# cfc-sensor-card.net
KiCad netlist of a schematic drawn in EAGLE
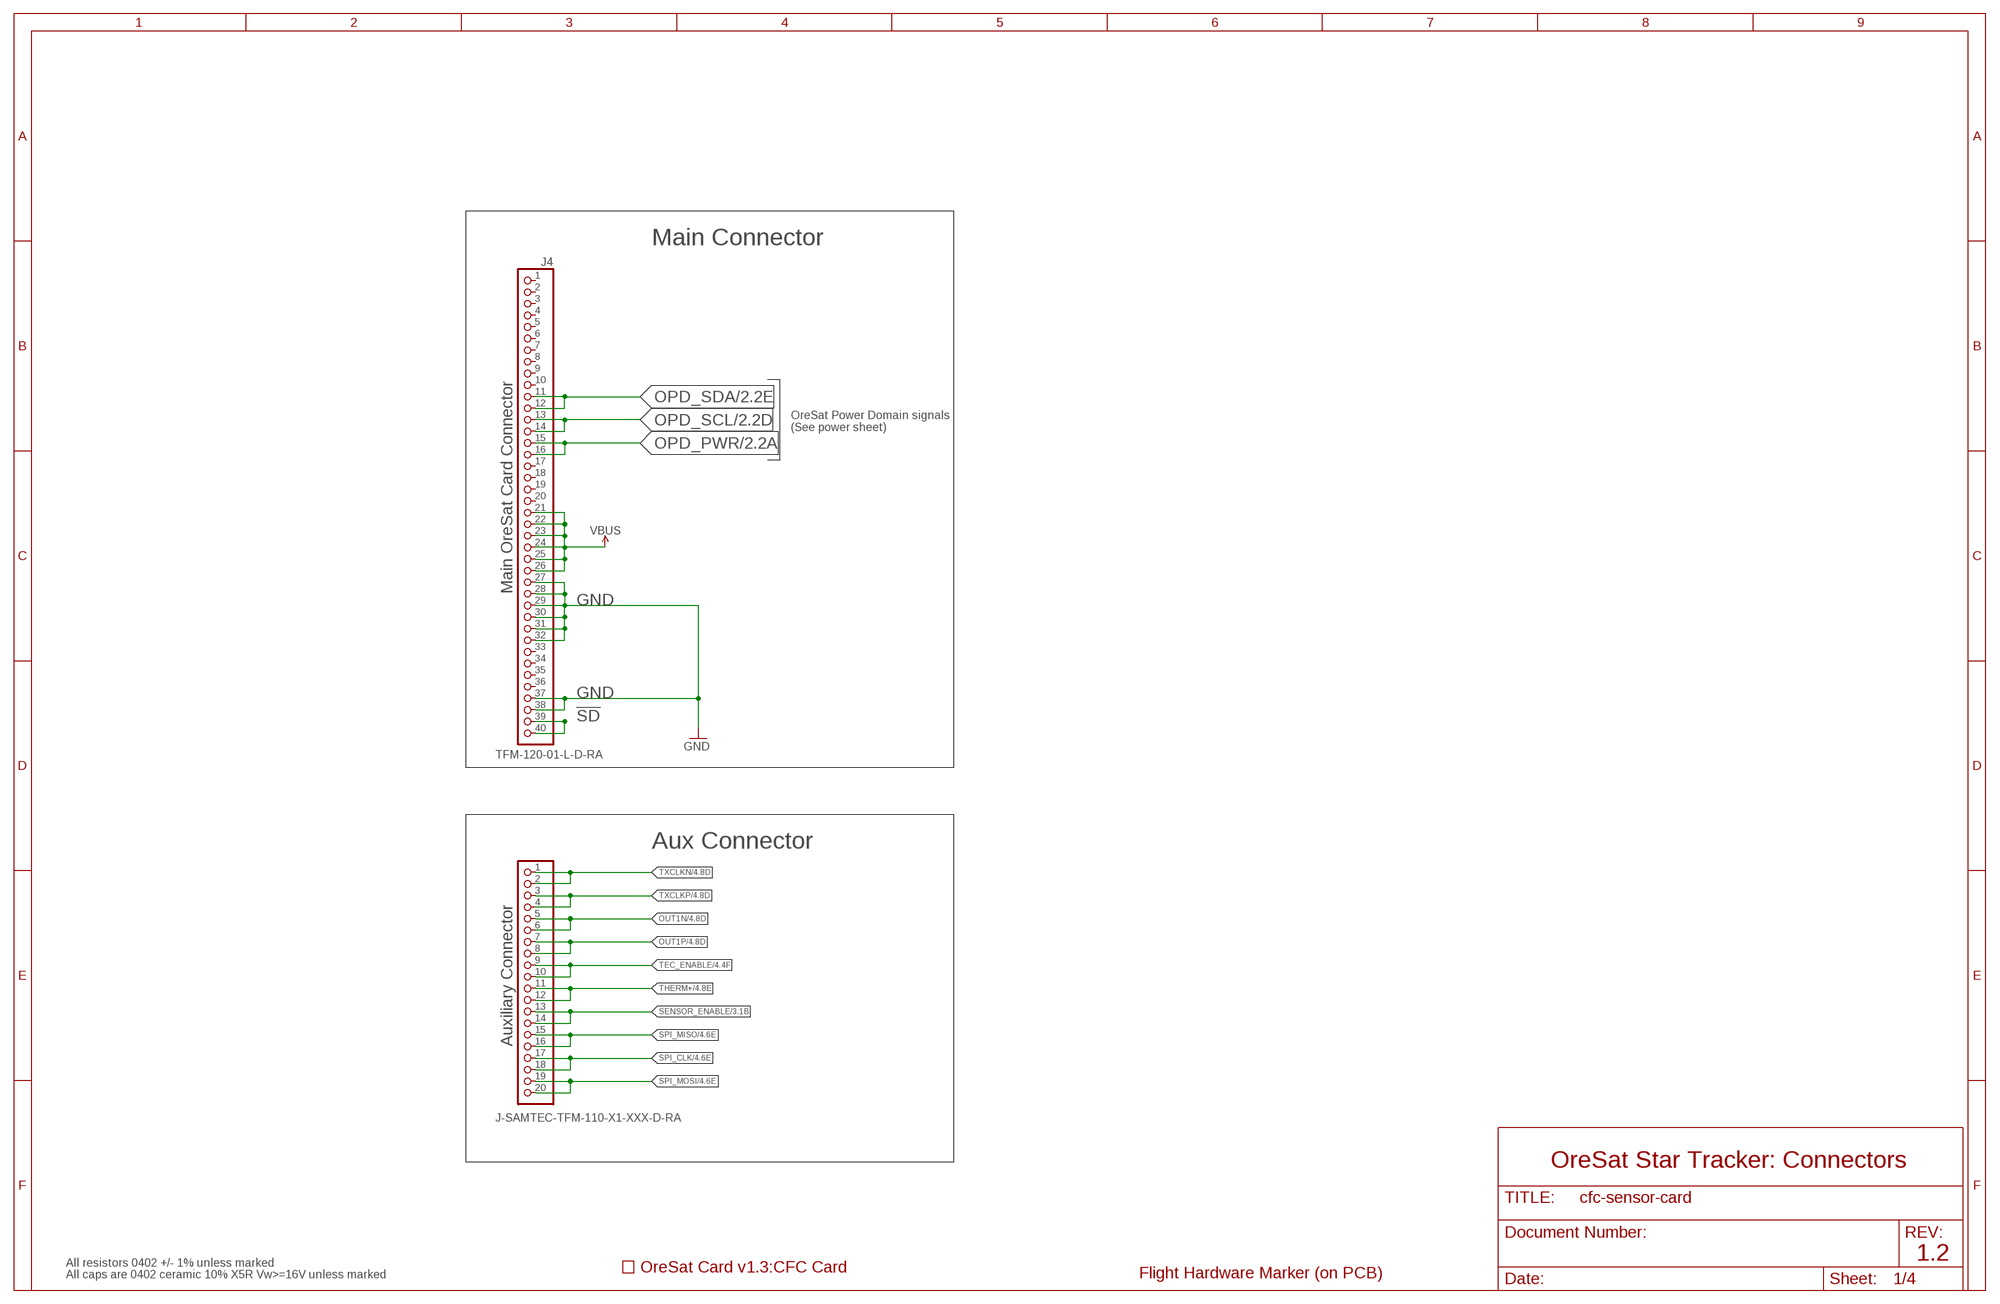
[diagram p0: schematic, sheet 1]
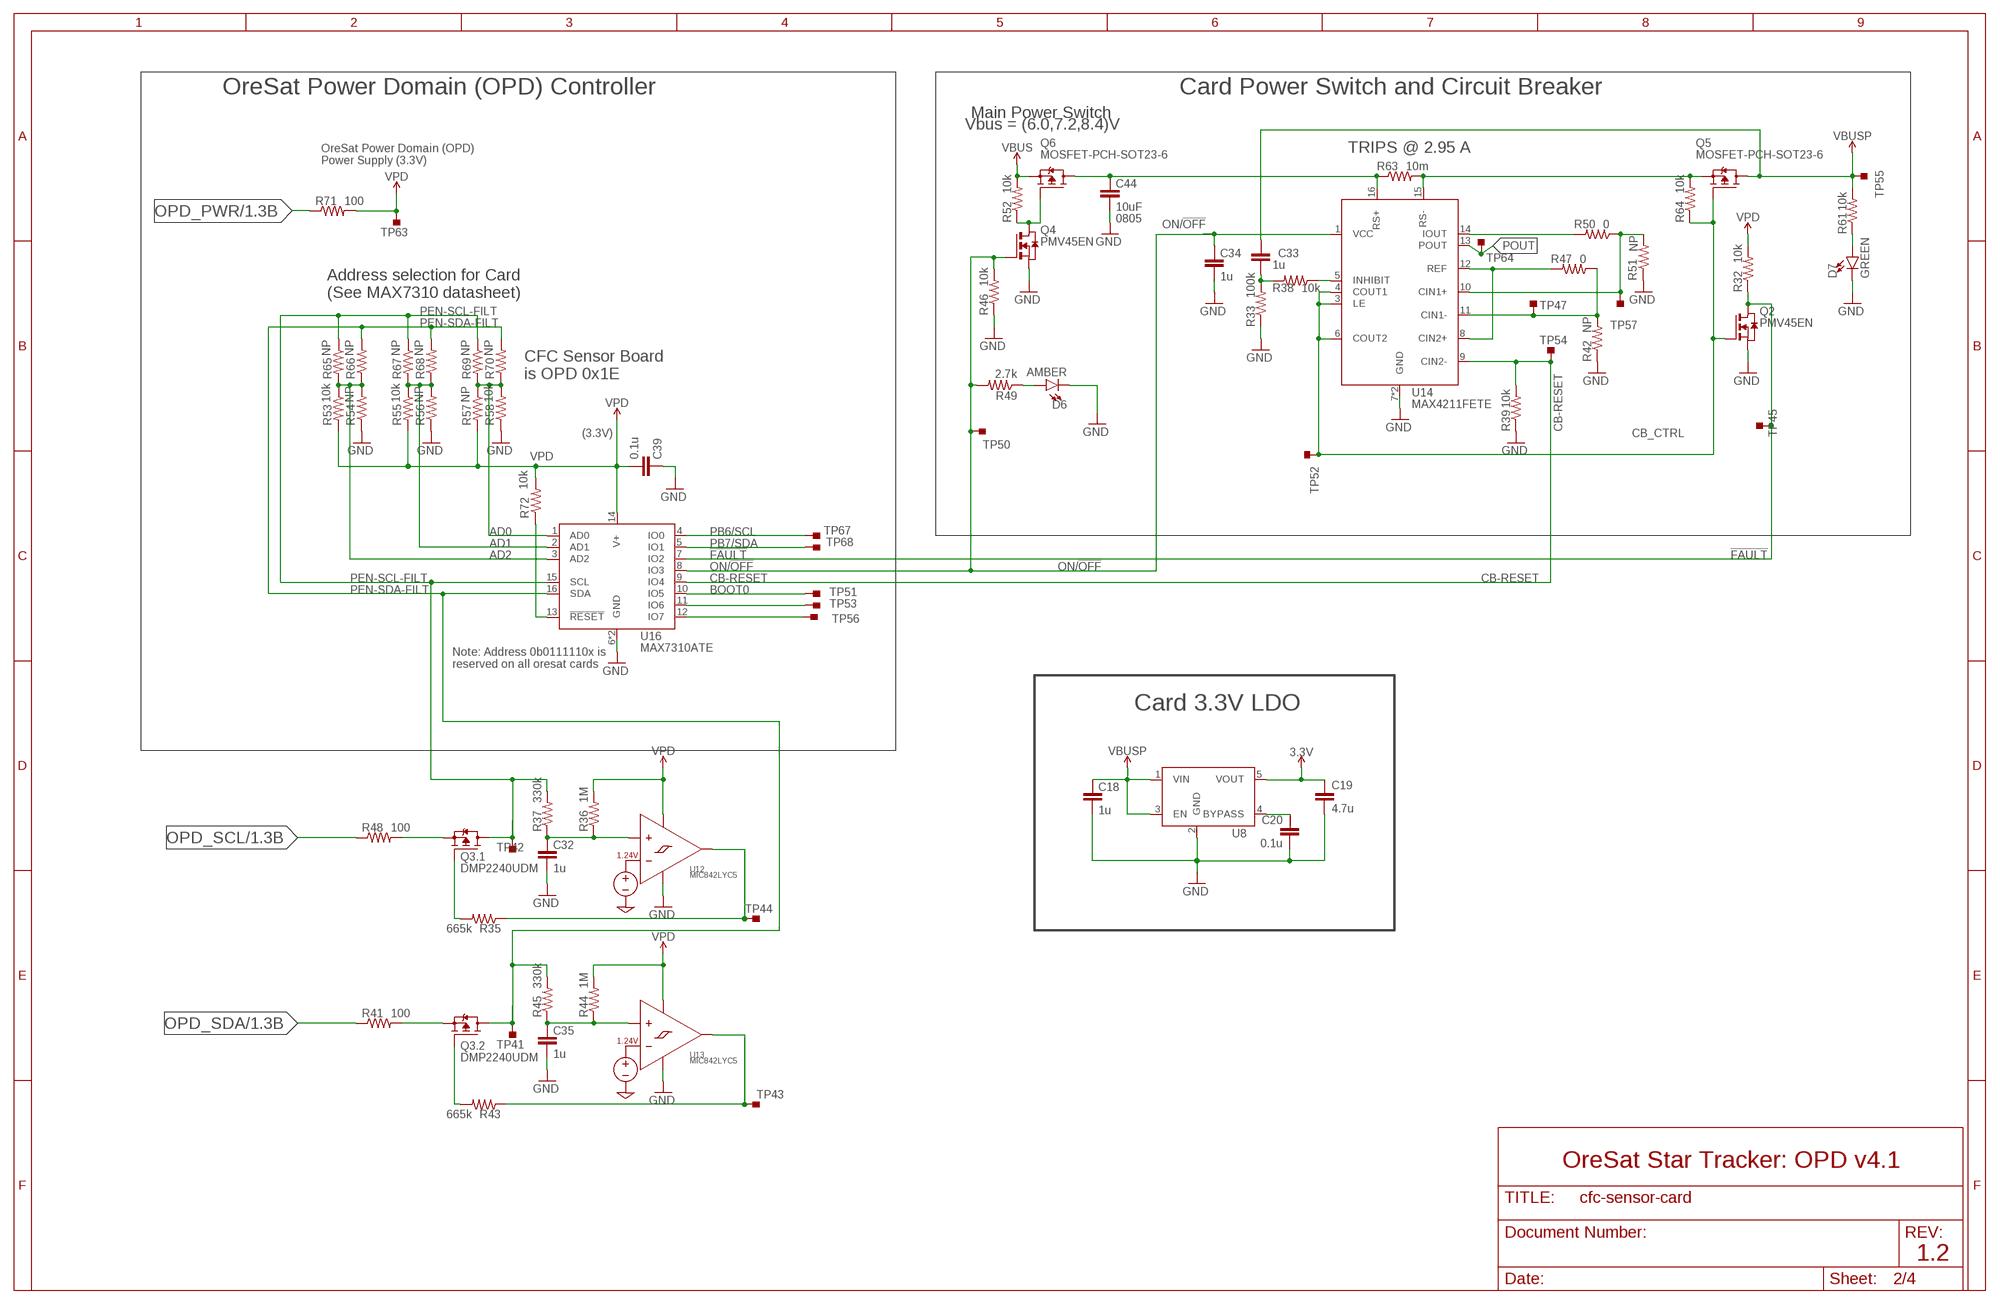
[diagram p1: schematic, sheet 2]
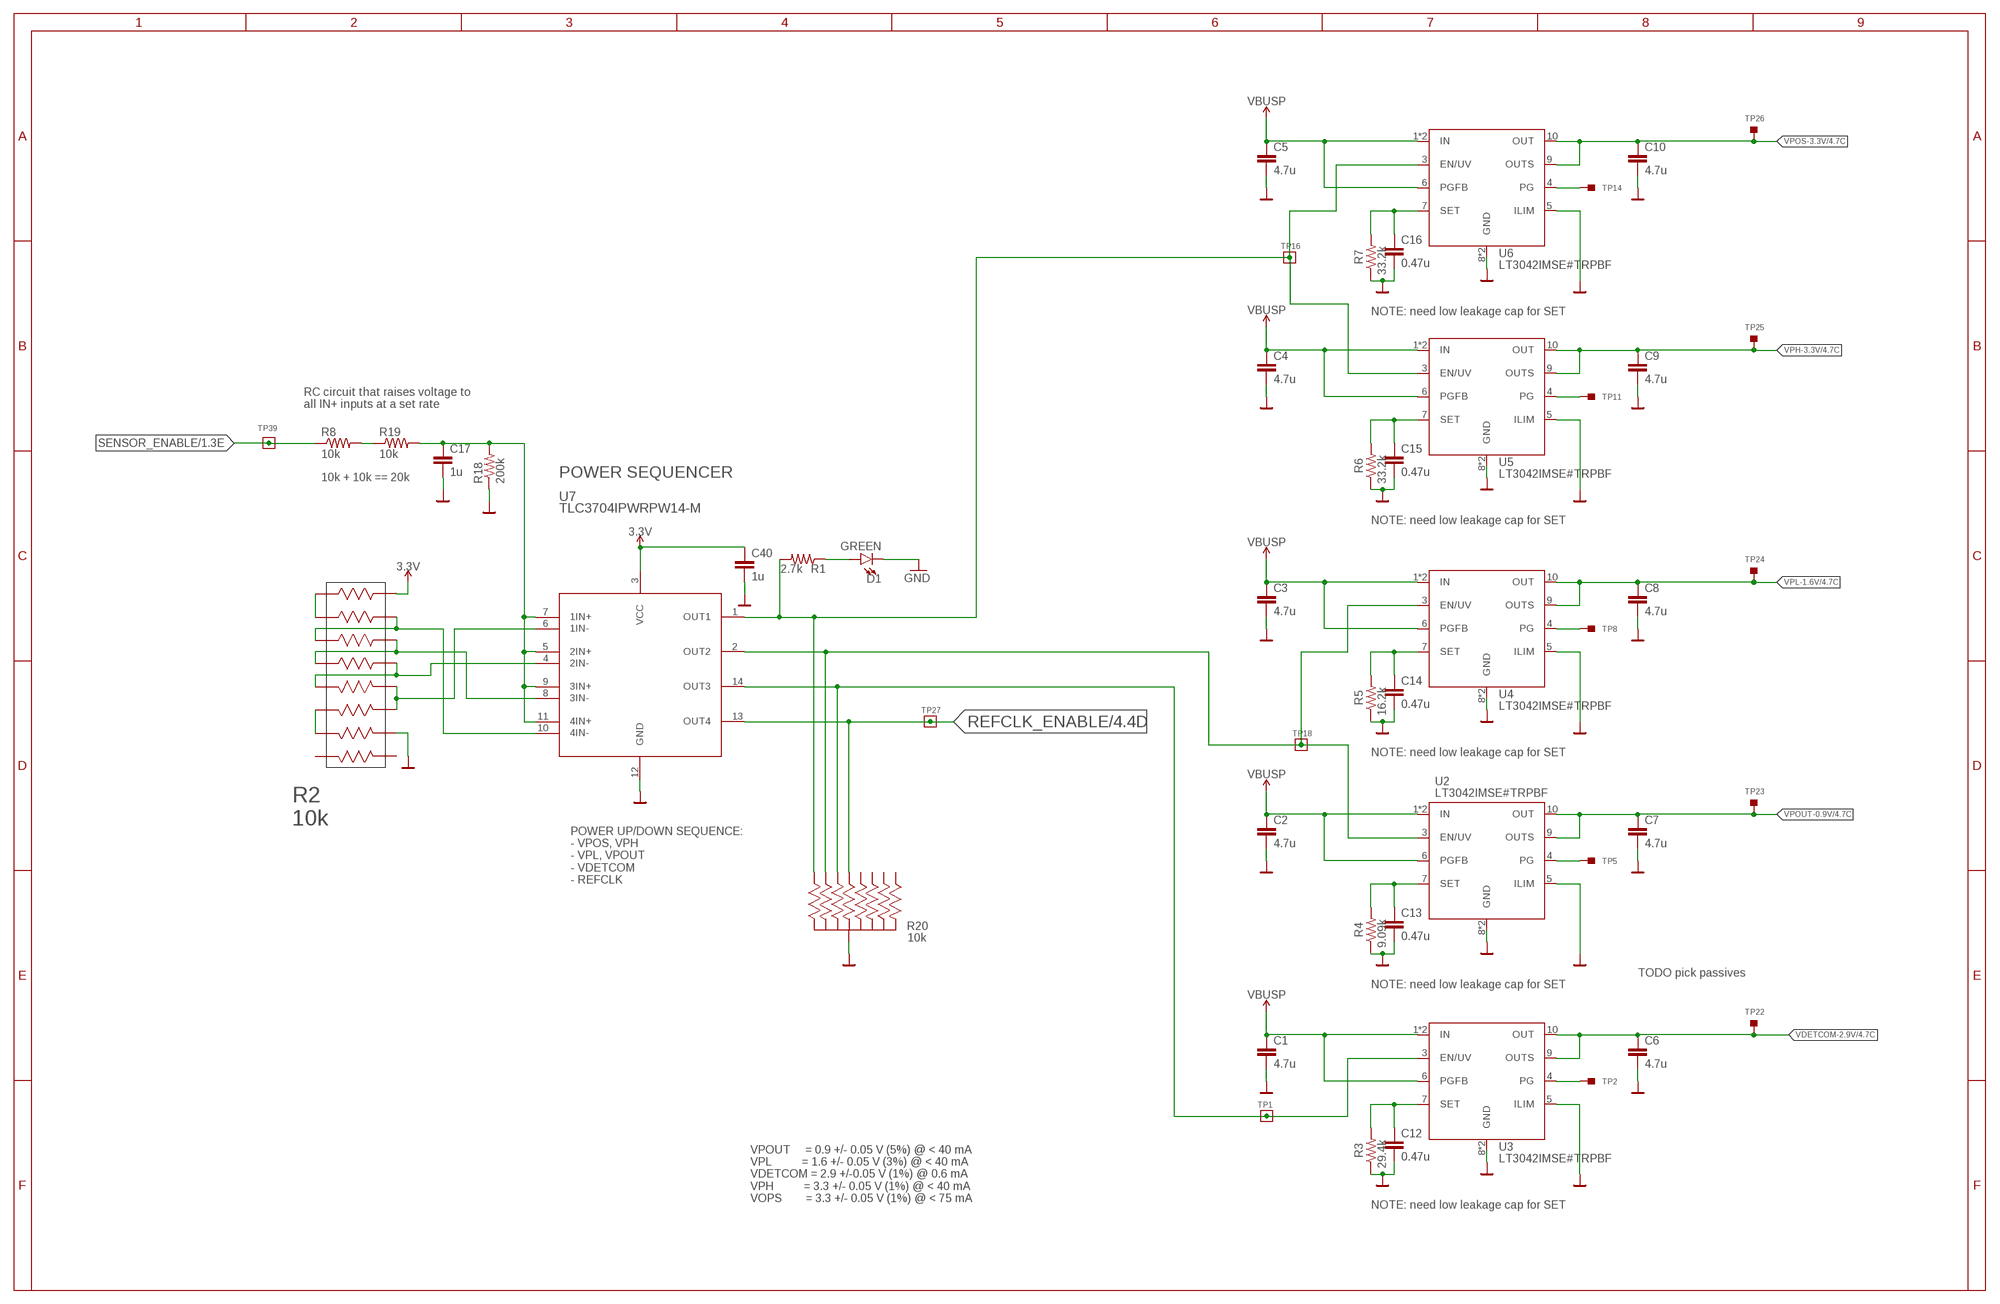
[diagram p2: schematic, sheet 3]
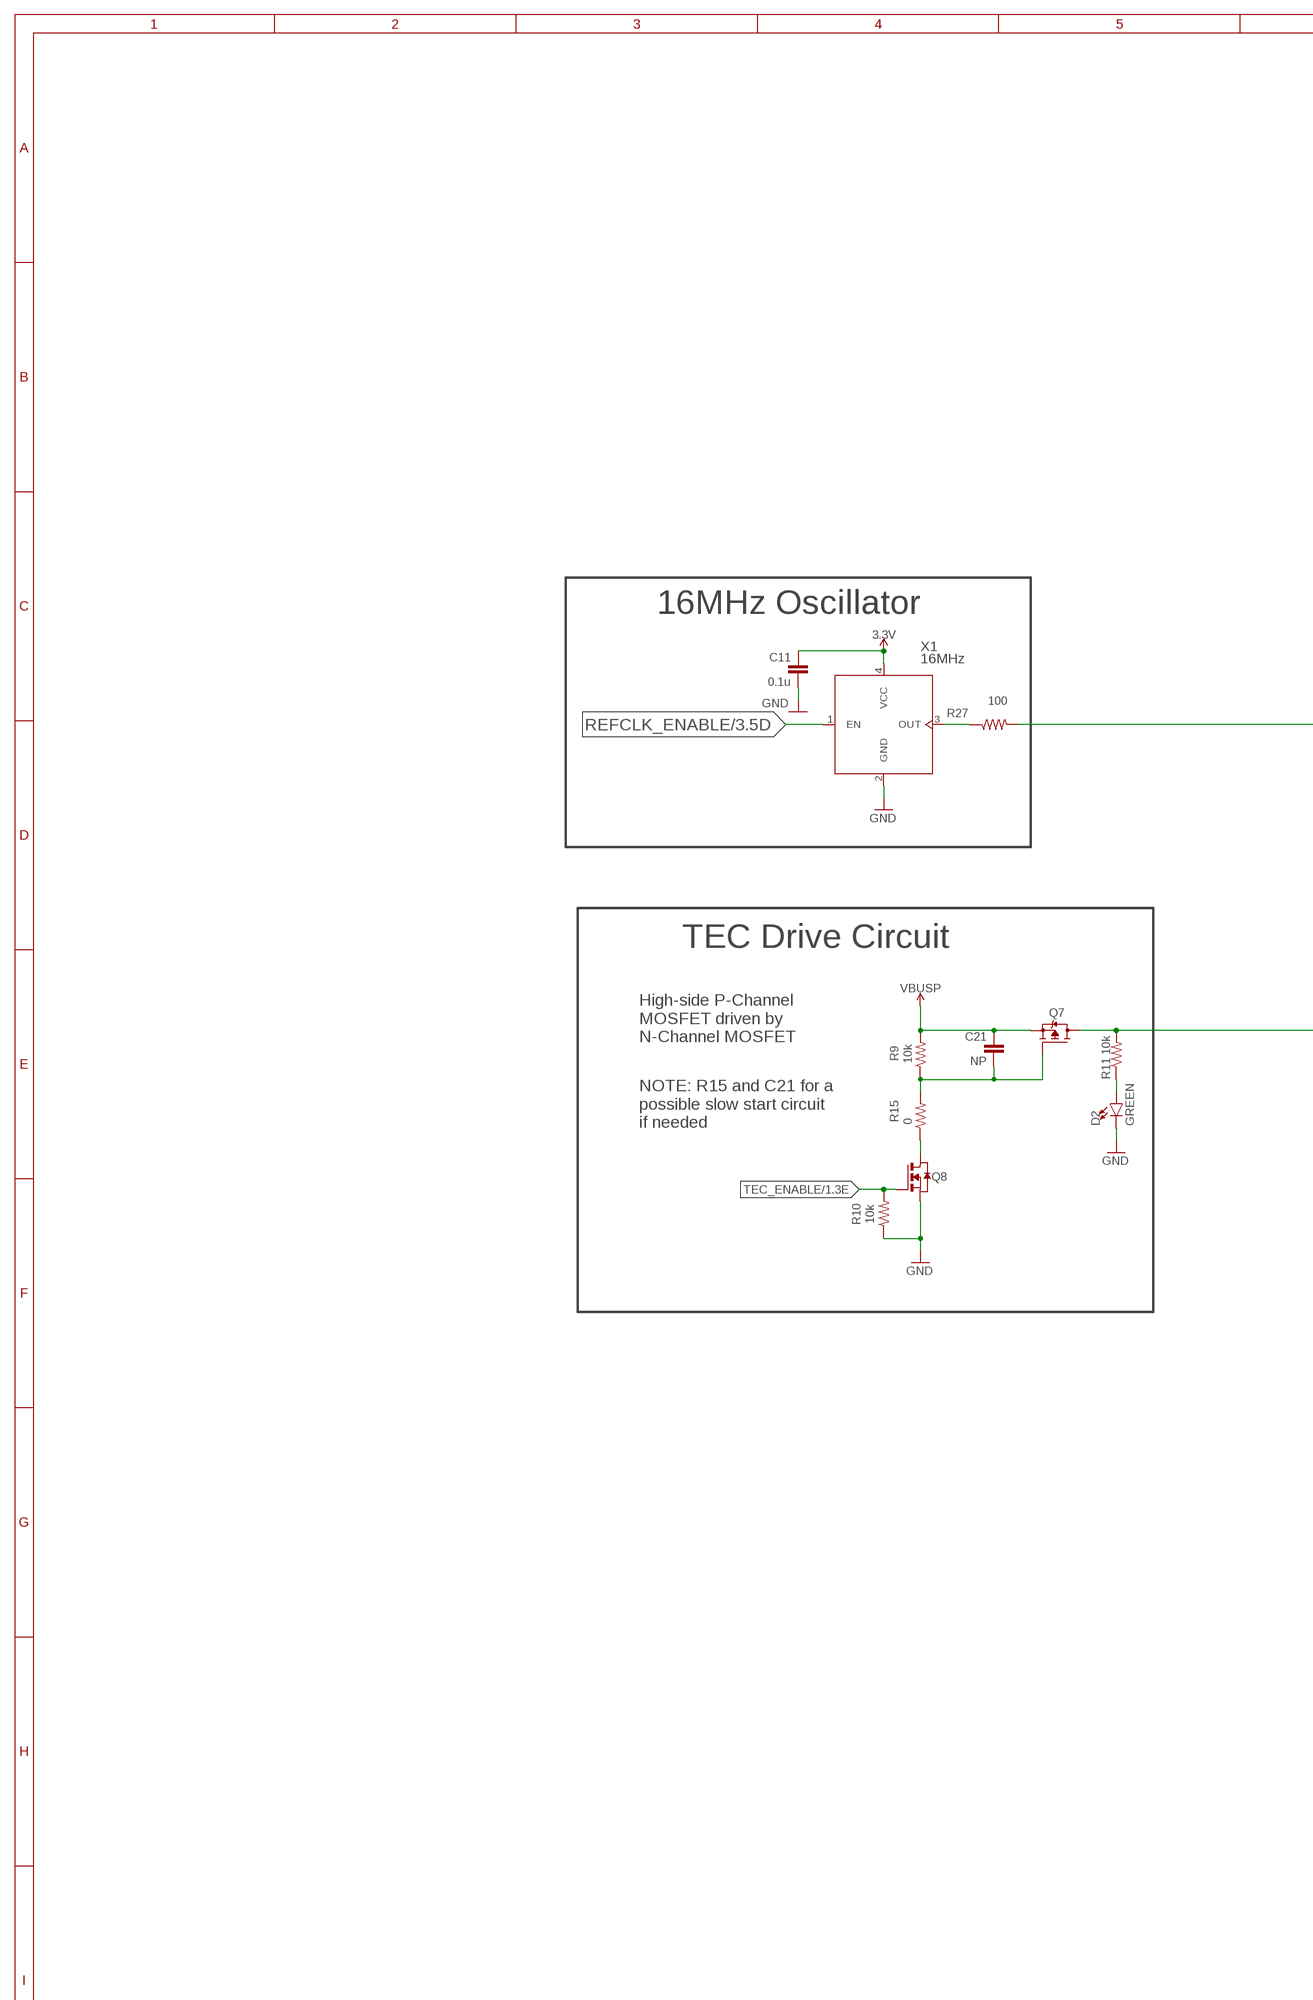
[diagram p3: schematic, sheet 4, part 1 of 2]
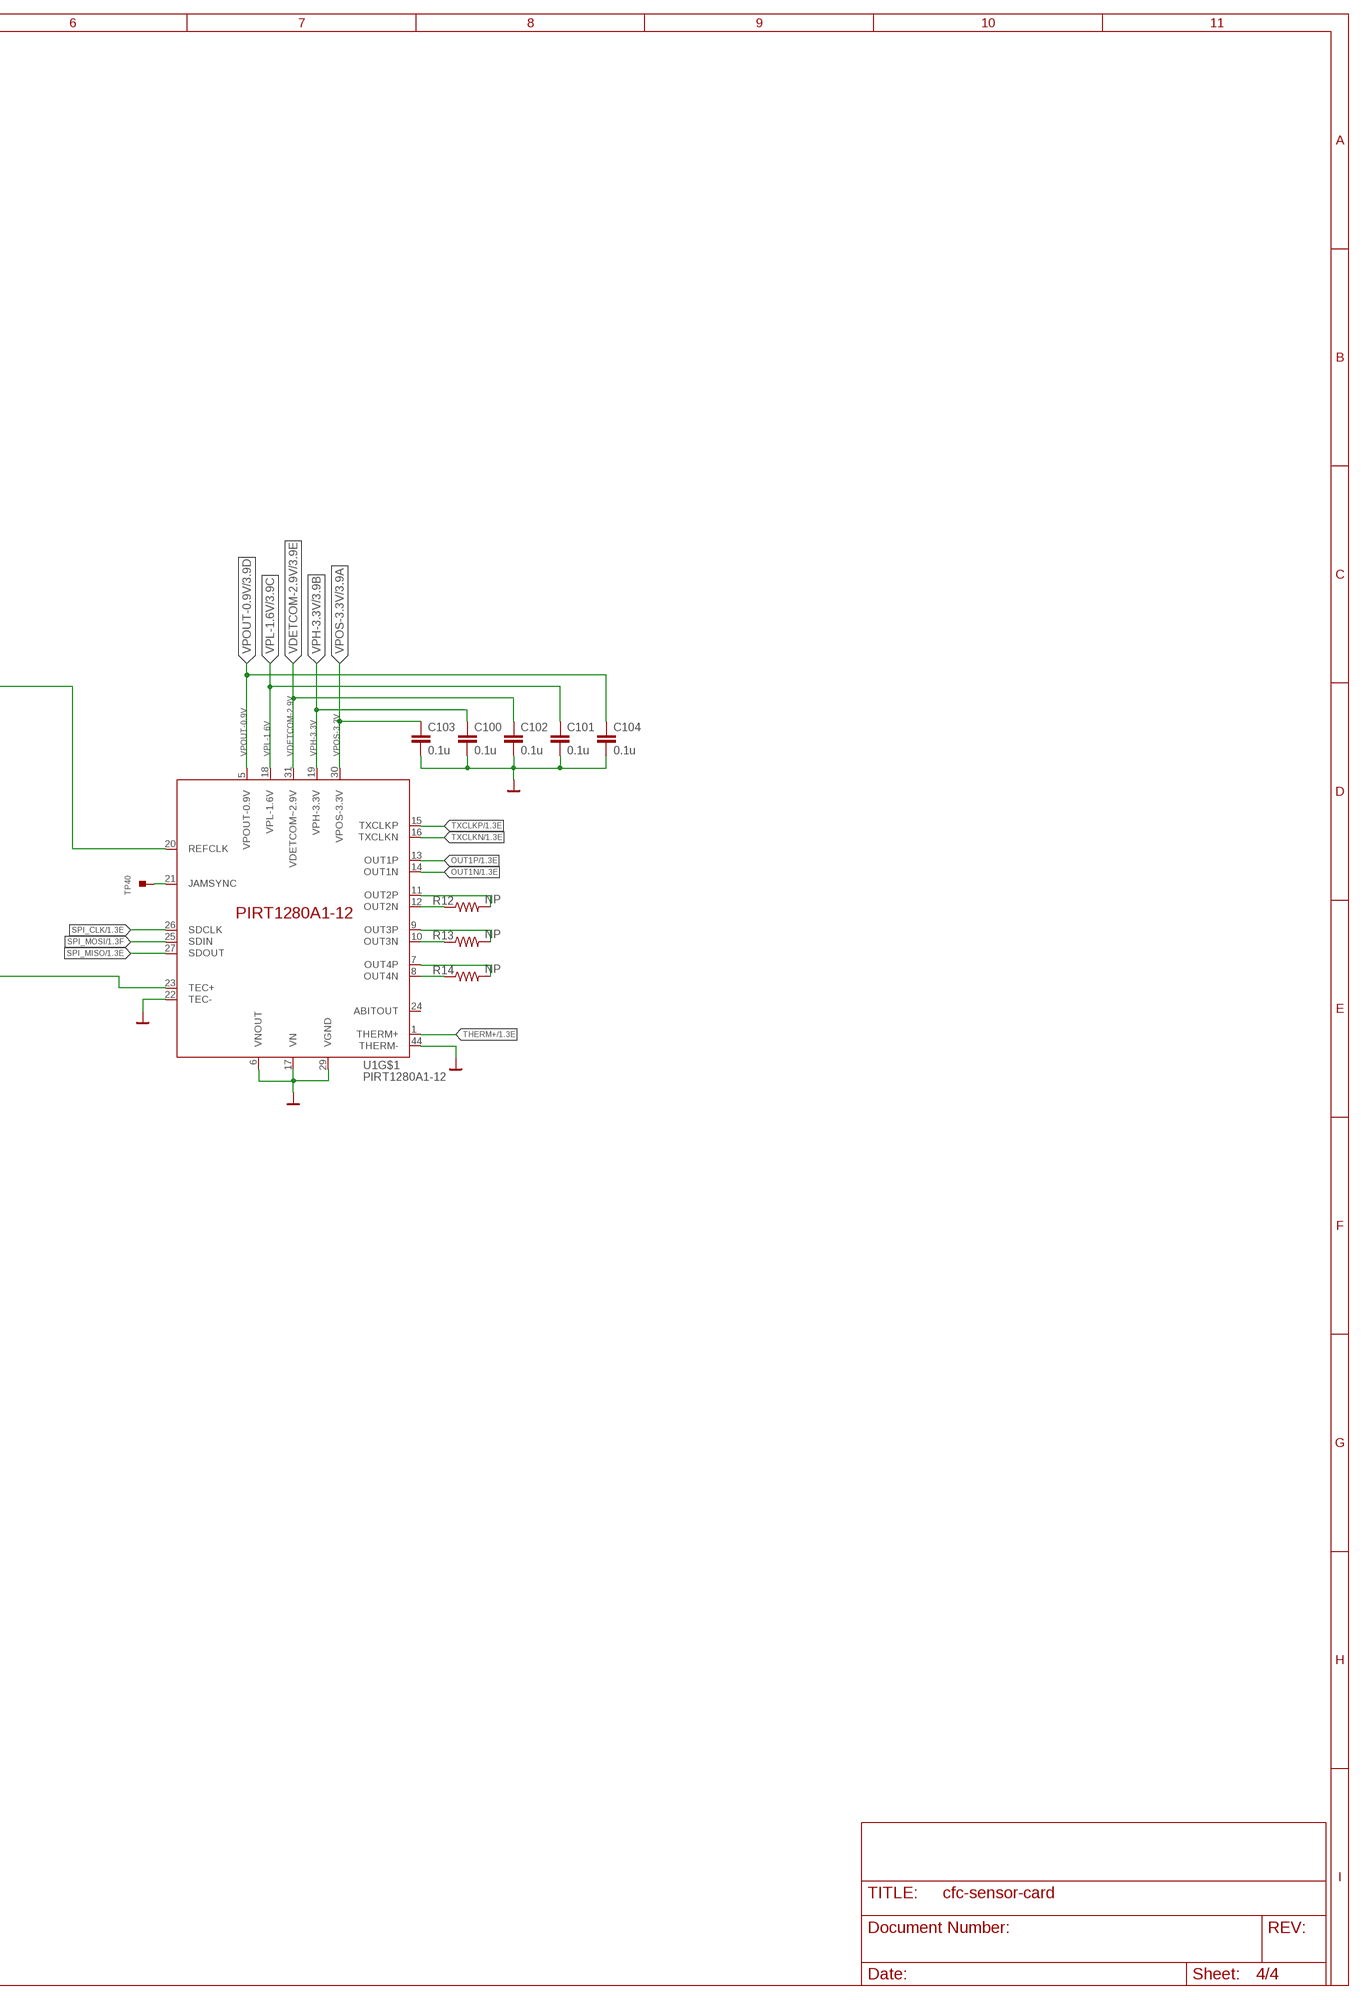
[diagram p4: schematic, sheet 4, part 2 of 2]

(export (version "E")
  (design (tool "Eeschema 10.0.6"))
  (components
    (comp (ref "C18")
      (value "1u")
      (footprint "eagle-import:.0603-B")
      (libsource (lib "eagle-import") (part "C-EU0603-B"))
    )
    (comp (ref "C19")
      (value "4.7u")
      (footprint "eagle-import:.0603-B")
      (libsource (lib "eagle-import") (part "C-EU0603-B"))
    )
    (comp (ref "C20")
      (value "0.1u")
      (footprint "eagle-import:.0603-B")
      (libsource (lib "eagle-import") (part "C-EU0603-B"))
    )
    (comp (ref "C32")
      (value "1u")
      (footprint "eagle-import:.0603-B")
      (libsource (lib "eagle-import") (part "C-EU0603-B"))
    )
    (comp (ref "C33")
      (value "1u")
      (footprint "eagle-import:.0603-B")
      (libsource (lib "eagle-import") (part "C-EU0603-B"))
    )
    (comp (ref "C34")
      (value "1u")
      (footprint "eagle-import:.0603-B")
      (libsource (lib "eagle-import") (part "C-EU0603-B"))
    )
    (comp (ref "C35")
      (value "1u")
      (footprint "eagle-import:.0603-B")
      (libsource (lib "eagle-import") (part "C-EU0603-B"))
    )
    (comp (ref "C39")
      (value "0.1u")
      (footprint "eagle-import:.0603-B")
      (libsource (lib "eagle-import") (part "C-EU0603-B"))
    )
    (comp (ref "C44")
      (value "10uF")
      (footprint "eagle-import:.0603-B")
      (libsource (lib "eagle-import") (part "C-EU0603-B"))
    )
    (comp (ref "D6")
      (value "AMBER")
      (footprint "eagle-import:LED-0603")
      (libsource (lib "eagle-import") (part "SparkFun-LED_529_LED-GREEN0603"))
    )
    (comp (ref "D7")
      (value "GREEN")
      (footprint "eagle-import:LED-0603")
      (libsource (lib "eagle-import") (part "LED-GREEN0603"))
    )
    (comp (ref "Q2")
      (value "PMV45EN")
      (footprint "eagle-import:SOT23")
      (fields (field (name "MPN") "PMV45EN2R"))
      (libsource (lib "eagle-import") (part "PMV45EN"))
    )
    (comp (ref "Q3")
      (value "DMP2240UDM")
      (footprint "eagle-import:SOT23-6")
      (fields (field (name "MFR") "Diodes Inc") (field (name "MPN") "DMP2240UDM-7"))
      (libsource (lib "eagle-import") (part "Q-MOSFET-PCH-dual-SOT23-6_MOSFET-PCH-SOT23-6"))
    )
    (comp (ref "Q4")
      (value "PMV45EN")
      (footprint "eagle-import:SOT23")
      (fields (field (name "MPN") "PMV45EN2R"))
      (libsource (lib "eagle-import") (part "PMV45EN"))
    )
    (comp (ref "Q5")
      (value "MOSFET-PCH-SOT23-6")
      (footprint "eagle-import:SOT23-6")
      (fields (field (name "MPN") "DMP3050LVT-7") (field (name "MPN_1") "DMP3050LVT-7"))
      (libsource (lib "eagle-import") (part "MOSFET-PCH-SOT23-6"))
    )
    (comp (ref "Q6")
      (value "MOSFET-PCH-SOT23-6")
      (footprint "eagle-import:SOT23-6")
      (fields (field (name "MPN") "DMP3050LVT-7") (field (name "MPN_1") "DMP3050LVT-7"))
      (libsource (lib "eagle-import") (part "MOSFET-PCH-SOT23-6"))
    )
    (comp (ref "R32")
      (value "10k")
      (footprint "eagle-import:.0603-B")
      (libsource (lib "eagle-import") (part "R-US_0603-B"))
    )
    (comp (ref "R33")
      (value "100k")
      (footprint "eagle-import:.0603-B")
      (fields (field (name "MFR") "Samsung") (field (name "MPN") "RC1005F6653CS"))
      (libsource (lib "eagle-import") (part "R-US_0603-B"))
    )
    (comp (ref "R35")
      (value "665k")
      (footprint "eagle-import:.0603-B")
      (libsource (lib "eagle-import") (part "R-US_0603-B"))
    )
    (comp (ref "R36")
      (value "1M")
      (footprint "eagle-import:.0603-B")
      (libsource (lib "eagle-import") (part "R-US_0603-B"))
    )
    (comp (ref "R37")
      (value "330k")
      (footprint "eagle-import:.0603-B")
      (libsource (lib "eagle-import") (part "R-US_0603-B"))
    )
    (comp (ref "R38")
      (value "10k")
      (footprint "eagle-import:.0603-B")
      (fields (field (name "MFR") "Samsung") (field (name "MPN") "RC1005F6653CS"))
      (libsource (lib "eagle-import") (part "R-US_0603-B"))
    )
    (comp (ref "R39")
      (value "10k")
      (footprint "eagle-import:.0603-B")
      (libsource (lib "eagle-import") (part "R-US_0603-B"))
    )
    (comp (ref "R41")
      (value "100")
      (footprint "eagle-import:.0603-B")
      (libsource (lib "eagle-import") (part "R-US_0603-B"))
    )
    (comp (ref "R42")
      (value "NP")
      (footprint "eagle-import:.0603-B")
      (fields (field (name "MFR") "Samsung") (field (name "MPN") "RC1005F6653CS"))
      (libsource (lib "eagle-import") (part "R-US_0603-B"))
    )
    (comp (ref "R43")
      (value "665k")
      (footprint "eagle-import:.0603-B")
      (libsource (lib "eagle-import") (part "R-US_0603-B"))
    )
    (comp (ref "R44")
      (value "1M")
      (footprint "eagle-import:.0603-B")
      (libsource (lib "eagle-import") (part "R-US_0603-B"))
    )
    (comp (ref "R45")
      (value "330k")
      (footprint "eagle-import:.0603-B")
      (libsource (lib "eagle-import") (part "R-US_0603-B"))
    )
    (comp (ref "R46")
      (value "10k")
      (footprint "eagle-import:.0603-B")
      (libsource (lib "eagle-import") (part "R-US_0603-B"))
    )
    (comp (ref "R47")
      (value "0")
      (footprint "eagle-import:.0603-B")
      (libsource (lib "eagle-import") (part "R-US_0603-B"))
    )
    (comp (ref "R48")
      (value "100")
      (footprint "eagle-import:.0603-B")
      (libsource (lib "eagle-import") (part "R-US_0603-B"))
    )
    (comp (ref "R49")
      (value "2.7k")
      (footprint "eagle-import:.0603-B")
      (libsource (lib "eagle-import") (part "R-US_0603-B"))
    )
    (comp (ref "R50")
      (value "0")
      (footprint "eagle-import:.0603-B")
      (libsource (lib "eagle-import") (part "R-US_0603-B"))
    )
    (comp (ref "R51")
      (value "NP")
      (footprint "eagle-import:.0603-B")
      (fields (field (name "MFR") "Samsung") (field (name "MPN") "RC1005F6653CS"))
      (libsource (lib "eagle-import") (part "R-US_0603-B"))
    )
    (comp (ref "R52")
      (value "10k")
      (footprint "eagle-import:.0603-B")
      (libsource (lib "eagle-import") (part "R-US_0603-B"))
    )
    (comp (ref "R53")
      (value "10k")
      (footprint "eagle-import:.0603-B")
      (fields (field (name "MFR") "Samsung") (field (name "MPN") "RC1005F6653CS"))
      (libsource (lib "eagle-import") (part "R-US_0603-B"))
    )
    (comp (ref "R54")
      (value "NP")
      (footprint "eagle-import:.0603-B")
      (fields (field (name "MFR") "Samsung") (field (name "MPN") "RC1005F6653CS"))
      (libsource (lib "eagle-import") (part "R-US_0603-B"))
    )
    (comp (ref "R55")
      (value "10k")
      (footprint "eagle-import:.0603-B")
      (fields (field (name "MFR") "Samsung") (field (name "MPN") "RC1005F6653CS"))
      (libsource (lib "eagle-import") (part "R-US_0603-B"))
    )
    (comp (ref "R56")
      (value "NP")
      (footprint "eagle-import:.0603-B")
      (fields (field (name "MFR") "Samsung") (field (name "MPN") "RC1005F6653CS"))
      (libsource (lib "eagle-import") (part "R-US_0603-B"))
    )
    (comp (ref "R57")
      (value "NP")
      (footprint "eagle-import:.0603-B")
      (fields (field (name "MFR") "Samsung") (field (name "MPN") "RC1005F6653CS"))
      (libsource (lib "eagle-import") (part "R-US_0603-B"))
    )
    (comp (ref "R58")
      (value "10k")
      (footprint "eagle-import:.0603-B")
      (fields (field (name "MFR") "Samsung") (field (name "MPN") "RC1005F6653CS"))
      (libsource (lib "eagle-import") (part "R-US_0603-B"))
    )
    (comp (ref "R61")
      (value "10k")
      (footprint "eagle-import:.0603-B")
      (libsource (lib "eagle-import") (part "R-US_0603-B"))
    )
    (comp (ref "R63")
      (value "10m")
      (footprint "eagle-import:R1206")
      (libsource (lib "eagle-import") (part "rcl_334_R-US_R1206"))
    )
    (comp (ref "R64")
      (value "10k")
      (footprint "eagle-import:.0603-B")
      (libsource (lib "eagle-import") (part "R-US_0603-B"))
    )
    (comp (ref "R65")
      (value "NP")
      (footprint "eagle-import:.0603-B")
      (fields (field (name "MFR") "Samsung") (field (name "MPN") "RC1005F6653CS"))
      (libsource (lib "eagle-import") (part "R-US_0603-B"))
    )
    (comp (ref "R66")
      (value "NP")
      (footprint "eagle-import:.0603-B")
      (fields (field (name "MFR") "Samsung") (field (name "MPN") "RC1005F6653CS"))
      (libsource (lib "eagle-import") (part "R-US_0603-B"))
    )
    (comp (ref "R67")
      (value "NP")
      (footprint "eagle-import:.0603-B")
      (fields (field (name "MFR") "Samsung") (field (name "MPN") "RC1005F6653CS"))
      (libsource (lib "eagle-import") (part "R-US_0603-B"))
    )
    (comp (ref "R68")
      (value "NP")
      (footprint "eagle-import:.0603-B")
      (fields (field (name "MFR") "Samsung") (field (name "MPN") "RC1005F6653CS"))
      (libsource (lib "eagle-import") (part "R-US_0603-B"))
    )
    (comp (ref "R69")
      (value "NP")
      (footprint "eagle-import:.0603-B")
      (fields (field (name "MFR") "Samsung") (field (name "MPN") "RC1005F6653CS"))
      (libsource (lib "eagle-import") (part "R-US_0603-B"))
    )
    (comp (ref "R70")
      (value "NP")
      (footprint "eagle-import:.0603-B")
      (fields (field (name "MFR") "Samsung") (field (name "MPN") "RC1005F6653CS"))
      (libsource (lib "eagle-import") (part "R-US_0603-B"))
    )
    (comp (ref "R71")
      (value "100")
      (footprint "eagle-import:.0603-B")
      (libsource (lib "eagle-import") (part "R-US_0603-B"))
    )
    (comp (ref "R72")
      (value "10k")
      (footprint "eagle-import:.0603-B")
      (libsource (lib "eagle-import") (part "R-US_0603-B"))
    )
    (comp (ref "TP41")
      (value "TEST-POINT_SMD-SMD-10SN")
      (footprint "eagle-import:TESTPOINT_SMD-10SN")
      (libsource (lib "eagle-import") (part "TEST-POINT_SMD-SMD-10SN"))
    )
    (comp (ref "TP42")
      (value "TEST-POINT_SMD-SMD-10SN")
      (footprint "eagle-import:TESTPOINT_SMD-10SN")
      (libsource (lib "eagle-import") (part "TEST-POINT_SMD-SMD-10SN"))
    )
    (comp (ref "TP43")
      (value "TEST-POINT_SMD-SMD-10SN")
      (footprint "eagle-import:TESTPOINT_SMD-10SN")
      (libsource (lib "eagle-import") (part "TEST-POINT_SMD-SMD-10SN"))
    )
    (comp (ref "TP44")
      (value "TEST-POINT_SMD-SMD-10SN")
      (footprint "eagle-import:TESTPOINT_SMD-10SN")
      (libsource (lib "eagle-import") (part "TEST-POINT_SMD-SMD-10SN"))
    )
    (comp (ref "TP45")
      (value "TEST-POINT_SMD-SMD-10SN")
      (footprint "eagle-import:TESTPOINT_SMD-10SN")
      (libsource (lib "eagle-import") (part "TEST-POINT_SMD-SMD-10SN"))
    )
    (comp (ref "TP47")
      (value "TEST-POINT_SMD-SMD-10SN")
      (footprint "eagle-import:TESTPOINT_SMD-10SN")
      (libsource (lib "eagle-import") (part "TEST-POINT_SMD-SMD-10SN"))
    )
    (comp (ref "TP50")
      (value "TEST-POINT_SMD-SMD-10SN")
      (footprint "eagle-import:TESTPOINT_SMD-10SN")
      (libsource (lib "eagle-import") (part "TEST-POINT_SMD-SMD-10SN"))
    )
    (comp (ref "TP51")
      (value "TEST-POINT_SMD-SMD-10SN")
      (footprint "eagle-import:TESTPOINT_SMD-10SN")
      (libsource (lib "eagle-import") (part "TEST-POINT_SMD-SMD-10SN"))
    )
    (comp (ref "TP52")
      (value "TEST-POINT_SMD-SMD-10SN")
      (footprint "eagle-import:TESTPOINT_SMD-10SN")
      (libsource (lib "eagle-import") (part "TEST-POINT_SMD-SMD-10SN"))
    )
    (comp (ref "TP53")
      (value "TEST-POINT_SMD-SMD-10SN")
      (footprint "eagle-import:TESTPOINT_SMD-10SN")
      (libsource (lib "eagle-import") (part "TEST-POINT_SMD-SMD-10SN"))
    )
    (comp (ref "TP54")
      (value "TEST-POINT_SMD-SMD-10SN")
      (footprint "eagle-import:TESTPOINT_SMD-10SN")
      (libsource (lib "eagle-import") (part "TEST-POINT_SMD-SMD-10SN"))
    )
    (comp (ref "TP55")
      (value "TEST-POINT_SMD-SMD-10SN")
      (footprint "eagle-import:TESTPOINT_SMD-10SN")
      (libsource (lib "eagle-import") (part "TEST-POINT_SMD-SMD-10SN"))
    )
    (comp (ref "TP56")
      (value "TEST-POINT_SMD-SMD-10SN")
      (footprint "eagle-import:TESTPOINT_SMD-10SN")
      (libsource (lib "eagle-import") (part "TEST-POINT_SMD-SMD-10SN"))
    )
    (comp (ref "TP57")
      (value "TEST-POINT_SMD-SMD-10SN")
      (footprint "eagle-import:TESTPOINT_SMD-10SN")
      (libsource (lib "eagle-import") (part "TEST-POINT_SMD-SMD-10SN"))
    )
    (comp (ref "TP63")
      (value "TEST-POINT_SMD-SMD-10SN")
      (footprint "eagle-import:TESTPOINT_SMD-10SN")
      (libsource (lib "eagle-import") (part "TEST-POINT_SMD-SMD-10SN"))
    )
    (comp (ref "TP64")
      (value "TEST-POINT_SMD-SMD-10SN")
      (footprint "eagle-import:TESTPOINT_SMD-10SN")
      (libsource (lib "eagle-import") (part "TEST-POINT_SMD-SMD-10SN"))
    )
    (comp (ref "TP67")
      (value "TEST-POINT_SMD-SMD-10SN")
      (footprint "eagle-import:TESTPOINT_SMD-10SN")
      (libsource (lib "eagle-import") (part "TEST-POINT_SMD-SMD-10SN"))
    )
    (comp (ref "TP68")
      (value "TEST-POINT_SMD-SMD-10SN")
      (footprint "eagle-import:TESTPOINT_SMD-10SN")
      (libsource (lib "eagle-import") (part "TEST-POINT_SMD-SMD-10SN"))
    )
    (comp (ref "U8")
      (value "LP2985AIM5-3.3_NOPB")
      (footprint "eagle-import:SOT-23")
      (fields
        (field (name "MANUFACTURER_PART_NUMBER") "LP2985AIM5-3.3/NOPB")
        (field (name "MOUSER_PART_NUMBER") "926-2985AIM53.3/NOPB")
        (field (name "RS_PART_NUMBER") "6520033P")
      )
      (libsource (lib "eagle-import") (part "LP2985AIM5-3.3_NOPB"))
    )
    (comp (ref "U12")
      (value "MIC842LYC5")
      (footprint "eagle-import:SC70-5")
      (libsource (lib "eagle-import") (part "MIC842LYC5"))
    )
    (comp (ref "U13")
      (value "MIC842LYC5")
      (footprint "eagle-import:SC70-5")
      (libsource (lib "eagle-import") (part "MIC842LYC5"))
    )
    (comp (ref "U14")
      (value "MAX4211FETE")
      (footprint "eagle-import:QFN65P400X400X80-17T210")
      (fields (field (name "MPN") "MAX4211FETE+"))
      (libsource (lib "eagle-import") (part "MAX4211"))
    )
    (comp (ref "U16")
      (value "MAX7310ATE")
      (footprint "eagle-import:QFN65P400X400X80-17T210")
      (fields
        (field (name "MPN") "MAX7310ATE+")
        (field (name "MFR") "Maxim")
        (field (name "MPN_1") "MAX7310ATE")
      )
      (libsource (lib "eagle-import") (part "MAX7310"))
    )
    (comp (ref "J2")
      (value "J-SAMTEC-TFM-110-X1-XXX-D-RA")
      (footprint "eagle-import:J-SAMTEC-TFM-110-X1-XXX-D-RA")
      (fields (field (name "MFR") "Samtec") (field (name "MPN") "TFM-110-01-L-D-RA "))
      (libsource (lib "eagle-import") (part "J-SAMTEC-TFM-110-X1-XXX-D-RA"))
    )
    (comp (ref "J4")
      (value "TFM-120-01-L-D-RA")
      (footprint "eagle-import:J-SAMTEC-TFM-120-X1-XXX-D-RA")
      (libsource (lib "eagle-import") (part "J-SAMTEC-TFM-120-X1-XXX-D-RA"))
    )
    (comp (ref "PCB1")
      (value "ORESAT-CARD-V1.3-CFC")
      (footprint "eagle-import:ORESAT-CARD-V1.3-CFC")
      (libsource (lib "eagle-import") (part "ORESAT-CARD-V1.3-CFC"))
    )
    (comp (ref "U$1")
      (value "FLIGHMARKERNEW")
      (footprint "eagle-import:FLIGHTMARKER_NEW_BOARDS")
      (libsource (lib "eagle-import") (part "FLIGHMARKERNEW"))
    )
    (comp (ref "C1")
      (value "4.7u")
      (footprint "eagle-import:.0603-B")
      (libsource (lib "eagle-import") (part "C-EU0603-B"))
    )
    (comp (ref "C2")
      (value "4.7u")
      (footprint "eagle-import:.0603-B")
      (libsource (lib "eagle-import") (part "C-EU0603-B"))
    )
    (comp (ref "C3")
      (value "4.7u")
      (footprint "eagle-import:.0603-B")
      (libsource (lib "eagle-import") (part "C-EU0603-B"))
    )
    (comp (ref "C4")
      (value "4.7u")
      (footprint "eagle-import:.0603-B")
      (libsource (lib "eagle-import") (part "C-EU0603-B"))
    )
    (comp (ref "C5")
      (value "4.7u")
      (footprint "eagle-import:.0603-B")
      (libsource (lib "eagle-import") (part "C-EU0603-B"))
    )
    (comp (ref "C6")
      (value "4.7u")
      (footprint "eagle-import:.0603-B")
      (libsource (lib "eagle-import") (part "C-EU0603-B"))
    )
    (comp (ref "C7")
      (value "4.7u")
      (footprint "eagle-import:.0603-B")
      (libsource (lib "eagle-import") (part "C-EU0603-B"))
    )
    (comp (ref "C8")
      (value "4.7u")
      (footprint "eagle-import:.0603-B")
      (libsource (lib "eagle-import") (part "C-EU0603-B"))
    )
    (comp (ref "C9")
      (value "4.7u")
      (footprint "eagle-import:.0603-B")
      (libsource (lib "eagle-import") (part "C-EU0603-B"))
    )
    (comp (ref "C10")
      (value "4.7u")
      (footprint "eagle-import:.0603-B")
      (libsource (lib "eagle-import") (part "C-EU0603-B"))
    )
    (comp (ref "C12")
      (value "0.47u")
      (footprint "eagle-import:.0603-B")
      (libsource (lib "eagle-import") (part "C-EU0603-B"))
    )
    (comp (ref "C13")
      (value "0.47u")
      (footprint "eagle-import:.0603-B")
      (libsource (lib "eagle-import") (part "C-EU0603-B"))
    )
    (comp (ref "C14")
      (value "0.47u")
      (footprint "eagle-import:.0603-B")
      (libsource (lib "eagle-import") (part "C-EU0603-B"))
    )
    (comp (ref "C15")
      (value "0.47u")
      (footprint "eagle-import:.0603-B")
      (libsource (lib "eagle-import") (part "C-EU0603-B"))
    )
    (comp (ref "C16")
      (value "0.47u")
      (footprint "eagle-import:.0603-B")
      (libsource (lib "eagle-import") (part "C-EU0603-B"))
    )
    (comp (ref "C17")
      (value "1u")
      (footprint "eagle-import:.0603-B")
      (libsource (lib "eagle-import") (part "C-EU0603-B"))
    )
    (comp (ref "C40")
      (value "1u")
      (footprint "eagle-import:.0603-B")
      (libsource (lib "eagle-import") (part "C-EU0603-B"))
    )
    (comp (ref "D1")
      (value "GREEN")
      (footprint "eagle-import:LED-0603")
      (description "Green 573nm LED Indication - Discrete 2V 0603 (1608 Metric)")
      (fields
        (field (name "DIGI-KEY_PART_NUMBER") "732-12017-1-ND")
        (field (name "MANUFACTURER") "Würth Elektronik")
      )
      (libsource (lib "eagle-import") (part "LED-GREEN0603"))
    )
    (comp (ref "R1")
      (value "2.7k")
      (footprint "eagle-import:.0603-B")
      (libsource (lib "eagle-import") (part "R-US_0603-B"))
    )
    (comp (ref "R2")
      (value "10k")
      (footprint "eagle-import:RES_EXB2HV")
      (fields (field (name "MPN") "EXB-2HV103JV"))
      (libsource (lib "eagle-import") (part "EXB-2HV103JV-LEGACY"))
    )
    (comp (ref "R3")
      (value "29.4k")
      (footprint "eagle-import:.0603-B")
      (libsource (lib "eagle-import") (part "R-US_0603-B"))
    )
    (comp (ref "R4")
      (value "9.09k")
      (footprint "eagle-import:.0603-B")
      (libsource (lib "eagle-import") (part "R-US_0603-B"))
    )
    (comp (ref "R5")
      (value "16.2k")
      (footprint "eagle-import:.0603-B")
      (libsource (lib "eagle-import") (part "R-US_0603-B"))
    )
    (comp (ref "R6")
      (value "33.2k")
      (footprint "eagle-import:.0603-B")
      (libsource (lib "eagle-import") (part "R-US_0603-B"))
    )
    (comp (ref "R7")
      (value "33.2k")
      (footprint "eagle-import:.0603-B")
      (libsource (lib "eagle-import") (part "R-US_0603-B"))
    )
    (comp (ref "R8")
      (value "10k")
      (footprint "eagle-import:.0603-B")
      (libsource (lib "eagle-import") (part "R-US_0603-B"))
    )
    (comp (ref "R18")
      (value "200k")
      (footprint "eagle-import:.0603-B")
      (libsource (lib "eagle-import") (part "R-US_0603-B"))
    )
    (comp (ref "R19")
      (value "10k")
      (footprint "eagle-import:.0603-B")
      (libsource (lib "eagle-import") (part "R-US_0603-B"))
    )
    (comp (ref "R20")
      (value "10k")
      (footprint "eagle-import:ARRAY_EXBA-M")
      (fields (field (name "MFR") "Panasonic Electronic Components") (field (name "MPN") "EXB-A10P103J"))
      (libsource (lib "eagle-import") (part "EXB-A10P391JC_ARRAY_EXBA-M"))
    )
    (comp (ref "TP1")
      (value "TEST-POINT-LARGE-SQUARE")
      (footprint "eagle-import:1X01")
      (libsource (lib "eagle-import") (part "TEST-POINT-LARGE-SQUARE"))
    )
    (comp (ref "TP2")
      (value "TEST-POINT_SMD-SMD-10SN")
      (footprint "eagle-import:TESTPOINT_SMD-10SN")
      (libsource (lib "eagle-import") (part "TEST-POINT_SMD-SMD-10SN"))
    )
    (comp (ref "TP5")
      (value "TEST-POINT_SMD-SMD-10SN")
      (footprint "eagle-import:TESTPOINT_SMD-10SN")
      (libsource (lib "eagle-import") (part "TEST-POINT_SMD-SMD-10SN"))
    )
    (comp (ref "TP8")
      (value "TEST-POINT_SMD-SMD-10SN")
      (footprint "eagle-import:TESTPOINT_SMD-10SN")
      (libsource (lib "eagle-import") (part "TEST-POINT_SMD-SMD-10SN"))
    )
    (comp (ref "TP11")
      (value "TEST-POINT_SMD-SMD-10SN")
      (footprint "eagle-import:TESTPOINT_SMD-10SN")
      (libsource (lib "eagle-import") (part "TEST-POINT_SMD-SMD-10SN"))
    )
    (comp (ref "TP14")
      (value "TEST-POINT_SMD-SMD-10SN")
      (footprint "eagle-import:TESTPOINT_SMD-10SN")
      (libsource (lib "eagle-import") (part "TEST-POINT_SMD-SMD-10SN"))
    )
    (comp (ref "TP16")
      (value "TEST-POINT-LARGE-SQUARE")
      (footprint "eagle-import:1X01")
      (libsource (lib "eagle-import") (part "TEST-POINT-LARGE-SQUARE"))
    )
    (comp (ref "TP18")
      (value "TEST-POINT-LARGE-SQUARE")
      (footprint "eagle-import:1X01")
      (libsource (lib "eagle-import") (part "TEST-POINT-LARGE-SQUARE"))
    )
    (comp (ref "TP22")
      (value "TEST-POINT_SMD-SMD-10SN")
      (footprint "eagle-import:TESTPOINT_SMD-10SN")
      (libsource (lib "eagle-import") (part "TEST-POINT_SMD-SMD-10SN"))
    )
    (comp (ref "TP23")
      (value "TEST-POINT_SMD-SMD-10SN")
      (footprint "eagle-import:TESTPOINT_SMD-10SN")
      (libsource (lib "eagle-import") (part "TEST-POINT_SMD-SMD-10SN"))
    )
    (comp (ref "TP24")
      (value "TEST-POINT_SMD-SMD-10SN")
      (footprint "eagle-import:TESTPOINT_SMD-10SN")
      (libsource (lib "eagle-import") (part "TEST-POINT_SMD-SMD-10SN"))
    )
    (comp (ref "TP25")
      (value "TEST-POINT_SMD-SMD-10SN")
      (footprint "eagle-import:TESTPOINT_SMD-10SN")
      (libsource (lib "eagle-import") (part "TEST-POINT_SMD-SMD-10SN"))
    )
    (comp (ref "TP26")
      (value "TEST-POINT_SMD-SMD-10SN")
      (footprint "eagle-import:TESTPOINT_SMD-10SN")
      (libsource (lib "eagle-import") (part "TEST-POINT_SMD-SMD-10SN"))
    )
    (comp (ref "TP27")
      (value "TEST-POINT-LARGE-SQUARE")
      (footprint "eagle-import:1X01")
      (libsource (lib "eagle-import") (part "TEST-POINT-LARGE-SQUARE"))
    )
    (comp (ref "TP39")
      (value "TEST-POINT-LARGE-SQUARE")
      (footprint "eagle-import:1X01")
      (libsource (lib "eagle-import") (part "TEST-POINT-LARGE-SQUARE"))
    )
    (comp (ref "U2")
      (value "LT3042IMSE#TRPBF")
      (footprint "eagle-import:SOP50P490X110-11N")
      (fields (field (name "MF") "Analog Devices"))
      (libsource (lib "eagle-import") (part "LT3042IMSE#TRPBF"))
    )
    (comp (ref "U3")
      (value "LT3042IMSE#TRPBF")
      (footprint "eagle-import:SOP50P490X110-11N")
      (fields (field (name "MF") "Analog Devices"))
      (libsource (lib "eagle-import") (part "LT3042IMSE#TRPBF"))
    )
    (comp (ref "U4")
      (value "LT3042IMSE#TRPBF")
      (footprint "eagle-import:SOP50P490X110-11N")
      (fields (field (name "MF") "Analog Devices"))
      (libsource (lib "eagle-import") (part "LT3042IMSE#TRPBF"))
    )
    (comp (ref "U5")
      (value "LT3042IMSE#TRPBF")
      (footprint "eagle-import:SOP50P490X110-11N")
      (fields (field (name "MF") "Analog Devices"))
      (libsource (lib "eagle-import") (part "LT3042IMSE#TRPBF"))
    )
    (comp (ref "U6")
      (value "LT3042IMSE#TRPBF")
      (footprint "eagle-import:SOP50P490X110-11N")
      (fields (field (name "MF") "Analog Devices"))
      (libsource (lib "eagle-import") (part "LT3042IMSE#TRPBF"))
    )
    (comp (ref "U7")
      (value "TLC3704IPWRPW14-M")
      (footprint "eagle-import:14-TSSOP")
      (fields
        (field (name "GENERIC_PART_NUMBER") "LM2901-Q1")
        (field (name "MANUFACTURER") "Texas Instruments")
        (field (name "MPN") "LM2901QPWRQ1")
      )
      (libsource (lib "eagle-import") (part "TLC3704IPWRPW14-M"))
    )
    (comp (ref "C11")
      (value "0.1u")
      (footprint "eagle-import:.0603-B")
      (libsource (lib "eagle-import") (part "C-EU0603-B"))
    )
    (comp (ref "C21")
      (value "NP")
      (footprint "eagle-import:.0603-B")
      (libsource (lib "eagle-import") (part "C-EU0603-B"))
    )
    (comp (ref "C100")
      (value "0.1u")
      (footprint "eagle-import:.0603-B")
      (libsource (lib "eagle-import") (part "C-EU0603-B"))
    )
    (comp (ref "C101")
      (value "0.1u")
      (footprint "eagle-import:.0603-B")
      (libsource (lib "eagle-import") (part "C-EU0603-B"))
    )
    (comp (ref "C102")
      (value "0.1u")
      (footprint "eagle-import:.0603-B")
      (libsource (lib "eagle-import") (part "C-EU0603-B"))
    )
    (comp (ref "C103")
      (value "0.1u")
      (footprint "eagle-import:.0603-B")
      (libsource (lib "eagle-import") (part "C-EU0603-B"))
    )
    (comp (ref "C104")
      (value "0.1u")
      (footprint "eagle-import:.0603-B")
      (libsource (lib "eagle-import") (part "C-EU0603-B"))
    )
    (comp (ref "D2")
      (value "GREEN")
      (footprint "eagle-import:LED-0603")
      (description "Green 573nm LED Indication - Discrete 2V 0603 (1608 Metric)")
      (fields
        (field (name "DIGI-KEY_PART_NUMBER") "732-12017-1-ND")
        (field (name "MANUFACTURER") "Würth Elektronik")
      )
      (libsource (lib "eagle-import") (part "LED-GREEN0603"))
    )
    (comp (ref "Q7")
      (value "MOSFET-PCH-SOT23-6")
      (footprint "eagle-import:SOT23-6")
      (fields (field (name "MPN") "DMP3050LVT-7") (field (name "MPN_1") "DMP3050LVT-7"))
      (libsource (lib "eagle-import") (part "MOSFET-PCH-SOT23-6"))
    )
    (comp (ref "Q8")
      (value "PMV45EN")
      (footprint "eagle-import:SOT23")
      (fields (field (name "MPN") "PMV45EN2R"))
      (libsource (lib "eagle-import") (part "PMV45EN"))
    )
    (comp (ref "R9")
      (value "10k")
      (footprint "eagle-import:.0603-B")
      (libsource (lib "eagle-import") (part "R-US_0603-B"))
    )
    (comp (ref "R10")
      (value "10k")
      (footprint "eagle-import:.0603-B")
      (libsource (lib "eagle-import") (part "R-US_0603-B"))
    )
    (comp (ref "R11")
      (value "10k")
      (footprint "eagle-import:.0603-B")
      (libsource (lib "eagle-import") (part "R-US_0603-B"))
    )
    (comp (ref "R12")
      (value "NP")
      (footprint "eagle-import:.0402-C-NOSILK")
      (fields (field (name "MFR") "Yageo") (field (name "MPN") "RC0201FR-07100RL"))
      (libsource (lib "eagle-import") (part "R-US_0402-C-NOSILK"))
    )
    (comp (ref "R13")
      (value "NP")
      (footprint "eagle-import:.0402-C-NOSILK")
      (fields (field (name "MFR") "Yageo") (field (name "MPN") "RC0201FR-07100RL"))
      (libsource (lib "eagle-import") (part "R-US_0402-C-NOSILK"))
    )
    (comp (ref "R14")
      (value "NP")
      (footprint "eagle-import:.0402-C-NOSILK")
      (fields (field (name "MFR") "Yageo") (field (name "MPN") "RC0201FR-07100RL"))
      (libsource (lib "eagle-import") (part "R-US_0402-C-NOSILK"))
    )
    (comp (ref "R15")
      (value "0")
      (footprint "eagle-import:.0603-B")
      (libsource (lib "eagle-import") (part "R-US_0603-B"))
    )
    (comp (ref "R27")
      (value "100")
      (footprint "eagle-import:.0402-A")
      (fields (field (name "MFR") "Vishay") (field (name "MPN") "RCA0402100RFKEDHP"))
      (libsource (lib "eagle-import") (part "R-US_0402-A"))
    )
    (comp (ref "TP40")
      (value "TEST-POINT_SMD-SMD-10SN")
      (footprint "eagle-import:TESTPOINT_SMD-10SN")
      (libsource (lib "eagle-import") (part "TEST-POINT_SMD-SMD-10SN"))
    )
    (comp (ref "U1")
      (value "PIRT1280A1-12")
      (footprint "eagle-import:PIRT1280A1-12")
      (libsource (lib "eagle-import") (part "PIRT1280A1-12"))
    )
    (comp (ref "X1")
      (value "16MHz")
      (footprint "eagle-import:OSC_2.5X2.0")
      (fields (field (name "MPN") "ISM95-3251AH-16.000MHZ"))
      (libsource (lib "eagle-import") (part "OSC_GENERIC_2.5X2.0"))
    )
  )
  (nets
    (net (code "1") (name "3.3V") (class "Default")
      (node (ref "C11") (pin "1") (pinfunction "1_1") (pintype "passive"))
      (node (ref "C19") (pin "1") (pinfunction "1_1") (pintype "passive"))
      (node (ref "C40") (pin "1") (pinfunction "1_1") (pintype "passive"))
      (node (ref "R2") (pin "16") (pinfunction "16_16") (pintype "passive"))
      (node (ref "U7") (pin "3") (pinfunction "VCC_3") (pintype "power_in"))
      (node (ref "U8") (pin "5") (pinfunction "VOUT_5") (pintype "power_in"))
      (node (ref "X1") (pin "4") (pinfunction "VCC_4") (pintype "power_in"))
    )
    (net (code "2") (name "AD0") (class "Default")
      (node (ref "R57") (pin "1") (pinfunction "1_1") (pintype "passive"))
      (node (ref "R58") (pin "2") (pinfunction "2_2") (pintype "passive"))
      (node (ref "R69") (pin "2") (pinfunction "2_2") (pintype "passive"))
      (node (ref "R70") (pin "1") (pinfunction "1_1") (pintype "passive"))
      (node (ref "U16") (pin "1") (pinfunction "AD0_1") (pintype "input"))
    )
    (net (code "3") (name "AD1") (class "Default")
      (node (ref "R55") (pin "1") (pinfunction "1_1") (pintype "passive"))
      (node (ref "R56") (pin "2") (pinfunction "2_2") (pintype "passive"))
      (node (ref "R67") (pin "2") (pinfunction "2_2") (pintype "passive"))
      (node (ref "R68") (pin "1") (pinfunction "1_1") (pintype "passive"))
      (node (ref "U16") (pin "2") (pinfunction "AD1_2") (pintype "input"))
    )
    (net (code "4") (name "AD2") (class "Default")
      (node (ref "R53") (pin "1") (pinfunction "1_1") (pintype "passive"))
      (node (ref "R54") (pin "2") (pinfunction "2_2") (pintype "passive"))
      (node (ref "R65") (pin "2") (pinfunction "2_2") (pintype "passive"))
      (node (ref "R66") (pin "1") (pinfunction "1_1") (pintype "passive"))
      (node (ref "U16") (pin "3") (pinfunction "AD2_3") (pintype "input"))
    )
    (net (code "5") (name "BOOT0") (class "Default")
      (node (ref "TP51") (pin "TP") (pinfunction "1_TP") (pintype "passive"))
      (node (ref "U16") (pin "10") (pinfunction "IO5_10") (pintype "bidirectional"))
    )
    (net (code "6") (name "CB-RESET") (class "Default")
      (node (ref "R39") (pin "2") (pinfunction "2_2") (pintype "passive"))
      (node (ref "TP54") (pin "TP") (pinfunction "1_TP") (pintype "passive"))
      (node (ref "U14") (pin "9") (pinfunction "CIN2-_9") (pintype "input"))
      (node (ref "U16") (pin "9") (pinfunction "IO4_9") (pintype "bidirectional"))
    )
    (net (code "7") (name "CB_CTRL") (class "Default")
      (node (ref "Q2") (pin "1") (pinfunction "G_1") (pintype "passive"))
      (node (ref "Q5") (pin "3") (pinfunction "G_3") (pintype "passive"))
      (node (ref "R64") (pin "1") (pinfunction "1_1") (pintype "passive"))
      (node (ref "TP52") (pin "TP") (pinfunction "1_TP") (pintype "passive"))
      (node (ref "U14") (pin "3") (pinfunction "LE_3") (pintype "input"))
      (node (ref "U14") (pin "4") (pinfunction "COUT1_4") (pintype "open_collector"))
      (node (ref "U14") (pin "6") (pinfunction "COUT2_6") (pintype "open_collector"))
    )
    (net (code "8") (name "GND") (class "Default")
      (node (ref "C1") (pin "2") (pinfunction "2_2") (pintype "passive"))
      (node (ref "C10") (pin "2") (pinfunction "2_2") (pintype "passive"))
      (node (ref "C100") (pin "2") (pinfunction "2_2") (pintype "passive"))
      (node (ref "C101") (pin "2") (pinfunction "2_2") (pintype "passive"))
      (node (ref "C102") (pin "2") (pinfunction "2_2") (pintype "passive"))
      (node (ref "C103") (pin "2") (pinfunction "2_2") (pintype "passive"))
      (node (ref "C104") (pin "2") (pinfunction "2_2") (pintype "passive"))
      (node (ref "C11") (pin "2") (pinfunction "2_2") (pintype "passive"))
      (node (ref "C12") (pin "2") (pinfunction "2_2") (pintype "passive"))
      (node (ref "C13") (pin "2") (pinfunction "2_2") (pintype "passive"))
      (node (ref "C14") (pin "2") (pinfunction "2_2") (pintype "passive"))
      (node (ref "C15") (pin "2") (pinfunction "2_2") (pintype "passive"))
      (node (ref "C16") (pin "2") (pinfunction "2_2") (pintype "passive"))
      (node (ref "C17") (pin "2") (pinfunction "2_2") (pintype "passive"))
      (node (ref "C18") (pin "2") (pinfunction "2_2") (pintype "passive"))
      (node (ref "C19") (pin "2") (pinfunction "2_2") (pintype "passive"))
      (node (ref "C2") (pin "2") (pinfunction "2_2") (pintype "passive"))
      (node (ref "C20") (pin "2") (pinfunction "2_2") (pintype "passive"))
      (node (ref "C3") (pin "2") (pinfunction "2_2") (pintype "passive"))
      (node (ref "C32") (pin "2") (pinfunction "2_2") (pintype "passive"))
      (node (ref "C34") (pin "2") (pinfunction "2_2") (pintype "passive"))
      (node (ref "C35") (pin "2") (pinfunction "2_2") (pintype "passive"))
      (node (ref "C39") (pin "1") (pinfunction "1_1") (pintype "passive"))
      (node (ref "C4") (pin "2") (pinfunction "2_2") (pintype "passive"))
      (node (ref "C40") (pin "2") (pinfunction "2_2") (pintype "passive"))
      (node (ref "C44") (pin "2") (pinfunction "2_2") (pintype "passive"))
      (node (ref "C5") (pin "2") (pinfunction "2_2") (pintype "passive"))
      (node (ref "C6") (pin "2") (pinfunction "2_2") (pintype "passive"))
      (node (ref "C7") (pin "2") (pinfunction "2_2") (pintype "passive"))
      (node (ref "C8") (pin "2") (pinfunction "2_2") (pintype "passive"))
      (node (ref "C9") (pin "2") (pinfunction "2_2") (pintype "passive"))
      (node (ref "D1") (pin "C") (pinfunction "C_C") (pintype "passive"))
      (node (ref "D2") (pin "C") (pinfunction "C_C") (pintype "passive"))
      (node (ref "D6") (pin "C") (pinfunction "C_C") (pintype "passive"))
      (node (ref "D7") (pin "C") (pinfunction "C_C") (pintype "passive"))
      (node (ref "J4") (pin "27") (pinfunction "27_27") (pintype "passive"))
      (node (ref "J4") (pin "28") (pinfunction "28_28") (pintype "passive"))
      (node (ref "J4") (pin "29") (pinfunction "29_29") (pintype "passive"))
      (node (ref "J4") (pin "30") (pinfunction "30_30") (pintype "passive"))
      (node (ref "J4") (pin "31") (pinfunction "31_31") (pintype "passive"))
      (node (ref "J4") (pin "32") (pinfunction "32_32") (pintype "passive"))
      (node (ref "J4") (pin "37") (pinfunction "37_37") (pintype "passive"))
      (node (ref "J4") (pin "38") (pinfunction "38_38") (pintype "passive"))
      (node (ref "Q2") (pin "2") (pinfunction "S_2") (pintype "passive"))
      (node (ref "Q4") (pin "2") (pinfunction "S_2") (pintype "passive"))
      (node (ref "Q8") (pin "2") (pinfunction "S_2") (pintype "passive"))
      (node (ref "R10") (pin "1") (pinfunction "1_1") (pintype "passive"))
      (node (ref "R18") (pin "1") (pinfunction "1_1") (pintype "passive"))
      (node (ref "R2") (pin "10") (pinfunction "10_10") (pintype "passive"))
      (node (ref "R20") (pin "10") (pinfunction "55_10") (pintype "passive"))
      (node (ref "R20") (pin "5") (pinfunction "55_5") (pintype "passive"))
      (node (ref "R3") (pin "1") (pinfunction "1_1") (pintype "passive"))
      (node (ref "R33") (pin "1") (pinfunction "1_1") (pintype "passive"))
      (node (ref "R39") (pin "1") (pinfunction "1_1") (pintype "passive"))
      (node (ref "R4") (pin "1") (pinfunction "1_1") (pintype "passive"))
      (node (ref "R42") (pin "1") (pinfunction "1_1") (pintype "passive"))
      (node (ref "R46") (pin "1") (pinfunction "1_1") (pintype "passive"))
      (node (ref "R5") (pin "1") (pinfunction "1_1") (pintype "passive"))
      (node (ref "R51") (pin "1") (pinfunction "1_1") (pintype "passive"))
      (node (ref "R54") (pin "1") (pinfunction "1_1") (pintype "passive"))
      (node (ref "R56") (pin "1") (pinfunction "1_1") (pintype "passive"))
      (node (ref "R58") (pin "1") (pinfunction "1_1") (pintype "passive"))
      (node (ref "R6") (pin "1") (pinfunction "1_1") (pintype "passive"))
      (node (ref "R7") (pin "1") (pinfunction "1_1") (pintype "passive"))
      (node (ref "U1") (pin "17") (pinfunction "VN_17") (pintype "power_in"))
      (node (ref "U1") (pin "22") (pinfunction "TEC-_22") (pintype "passive"))
      (node (ref "U1") (pin "29") (pinfunction "VGND_29") (pintype "power_in"))
      (node (ref "U1") (pin "44") (pinfunction "THERM-_44") (pintype "passive"))
      (node (ref "U1") (pin "6") (pinfunction "VNOUT_6") (pintype "power_in"))
      (node (ref "U12") (pin "2") (pinfunction "GND_2") (pintype "power_in"))
      (node (ref "U13") (pin "2") (pinfunction "GND_2") (pintype "power_in"))
      (node (ref "U14") (pin "7") (pinfunction "GND_7") (pintype "power_in"))
      (node (ref "U14") (pin "EPAD") (pinfunction "GND_EPAD") (pintype "power_in"))
      (node (ref "U16") (pin "6") (pinfunction "GND_6") (pintype "power_in"))
      (node (ref "U16") (pin "EPAD") (pinfunction "GND_EPAD") (pintype "power_in"))
      (node (ref "U2") (pin "11") (pinfunction "GND_11") (pintype "power_in"))
      (node (ref "U2") (pin "5") (pinfunction "ILIM_5") (pintype "passive"))
      (node (ref "U2") (pin "8") (pinfunction "GND_8") (pintype "power_in"))
      (node (ref "U3") (pin "11") (pinfunction "GND_11") (pintype "power_in"))
      (node (ref "U3") (pin "5") (pinfunction "ILIM_5") (pintype "passive"))
      (node (ref "U3") (pin "8") (pinfunction "GND_8") (pintype "power_in"))
      (node (ref "U4") (pin "11") (pinfunction "GND_11") (pintype "power_in"))
      (node (ref "U4") (pin "5") (pinfunction "ILIM_5") (pintype "passive"))
      (node (ref "U4") (pin "8") (pinfunction "GND_8") (pintype "power_in"))
      (node (ref "U5") (pin "11") (pinfunction "GND_11") (pintype "power_in"))
      (node (ref "U5") (pin "5") (pinfunction "ILIM_5") (pintype "passive"))
      (node (ref "U5") (pin "8") (pinfunction "GND_8") (pintype "power_in"))
      (node (ref "U6") (pin "11") (pinfunction "GND_11") (pintype "power_in"))
      (node (ref "U6") (pin "5") (pinfunction "ILIM_5") (pintype "passive"))
      (node (ref "U6") (pin "8") (pinfunction "GND_8") (pintype "power_in"))
      (node (ref "U7") (pin "12") (pinfunction "GND_12") (pintype "power_in"))
      (node (ref "U8") (pin "2") (pinfunction "GND_2") (pintype "power_in"))
      (node (ref "X1") (pin "2") (pinfunction "GND_2") (pintype "power_in"))
    )
    (net (code "9") (name "Net-(C33-Pad1)") (class "Default")
      (node (ref "C33") (pin "1") (pinfunction "1_1") (pintype "passive"))
      (node (ref "R33") (pin "2") (pinfunction "2_2") (pintype "passive"))
      (node (ref "R38") (pin "2") (pinfunction "2_2") (pintype "passive"))
    )
    (net (code "10") (name "Net-(D1-PadA)") (class "Default")
      (node (ref "D1") (pin "A") (pinfunction "A_A") (pintype "passive"))
      (node (ref "R1") (pin "1") (pinfunction "1_1") (pintype "passive"))
    )
    (net (code "11") (name "Net-(D2-PadA)") (class "Default")
      (node (ref "D2") (pin "A") (pinfunction "A_A") (pintype "passive"))
      (node (ref "R11") (pin "1") (pinfunction "1_1") (pintype "passive"))
    )
    (net (code "12") (name "Net-(D6-PadA)") (class "Default")
      (node (ref "D6") (pin "A") (pinfunction "A_A") (pintype "passive"))
      (node (ref "R49") (pin "1") (pinfunction "1_1") (pintype "passive"))
    )
    (net (code "13") (name "Net-(D7-PadA)") (class "Default")
      (node (ref "D7") (pin "A") (pinfunction "A_A") (pintype "passive"))
      (node (ref "R61") (pin "1") (pinfunction "1_1") (pintype "passive"))
    )
    (net (code "14") (name "Net-(Q3A-G)") (class "Default")
      (node (ref "Q3") (pin "1") (pinfunction "G_1") (pintype "passive"))
      (node (ref "R35") (pin "2") (pinfunction "2_2") (pintype "passive"))
    )
    (net (code "15") (name "Net-(Q3A-S)") (class "Default")
      (node (ref "Q3") (pin "5") (pinfunction "S_5") (pintype "passive"))
      (node (ref "R48") (pin "2") (pinfunction "2_2") (pintype "passive"))
    )
    (net (code "16") (name "Net-(Q3B-G)") (class "Default")
      (node (ref "Q3") (pin "3") (pinfunction "G_3") (pintype "passive"))
      (node (ref "R43") (pin "2") (pinfunction "2_2") (pintype "passive"))
    )
    (net (code "17") (name "Net-(Q3B-S)") (class "Default")
      (node (ref "Q3") (pin "2") (pinfunction "S_2") (pintype "passive"))
      (node (ref "R41") (pin "2") (pinfunction "2_2") (pintype "passive"))
    )
    (net (code "18") (name "Net-(Q4-D)") (class "Default")
      (node (ref "Q4") (pin "3") (pinfunction "D_3") (pintype "passive"))
      (node (ref "Q6") (pin "3") (pinfunction "G_3") (pintype "passive"))
      (node (ref "R52") (pin "1") (pinfunction "1_1") (pintype "passive"))
    )
    (net (code "19") (name "Net-(Q5-S)") (class "Default")
      (node (ref "Q5") (pin "4") (pinfunction "S_4") (pintype "passive"))
      (node (ref "R63") (pin "2") (pinfunction "2_2") (pintype "passive"))
      (node (ref "R64") (pin "2") (pinfunction "2_2") (pintype "passive"))
      (node (ref "U14") (pin "15") (pinfunction "RS-_15") (pintype "passive"))
    )
    (net (code "20") (name "Net-(Q7-G)") (class "Default")
      (node (ref "C21") (pin "2") (pinfunction "2_2") (pintype "passive"))
      (node (ref "Q7") (pin "3") (pinfunction "G_3") (pintype "passive"))
      (node (ref "R15") (pin "2") (pinfunction "2_2") (pintype "passive"))
      (node (ref "R9") (pin "1") (pinfunction "1_1") (pintype "passive"))
    )
    (net (code "21") (name "Net-(Q8-D)") (class "Default")
      (node (ref "Q8") (pin "3") (pinfunction "D_3") (pintype "passive"))
      (node (ref "R15") (pin "1") (pinfunction "1_1") (pintype "passive"))
    )
    (net (code "22") (name "Net-(R2-Pad1)") (class "Default")
      (node (ref "R2") (pin "1") (pinfunction "1_1") (pintype "passive"))
      (node (ref "R2") (pin "2") (pinfunction "2_2") (pintype "passive"))
    )
    (net (code "23") (name "Net-(R2-Pad6)") (class "Default")
      (node (ref "R2") (pin "6") (pinfunction "6_6") (pintype "passive"))
      (node (ref "R2") (pin "7") (pinfunction "7_7") (pintype "passive"))
    )
    (net (code "24") (name "Net-(R19-Pad1)") (class "Default")
      (node (ref "R19") (pin "1") (pinfunction "1_1") (pintype "passive"))
      (node (ref "R8") (pin "2") (pinfunction "2_2") (pintype "passive"))
    )
    (net (code "25") (name "Net-(R20-44)") (class "Default")
      (node (ref "R20") (pin "4") (pinfunction "44_4") (pintype "passive"))
      (node (ref "TP18") (pin "1") (pinfunction "1_1") (pintype "passive"))
      (node (ref "U2") (pin "3") (pinfunction "EN/UV_3") (pintype "input"))
      (node (ref "U4") (pin "3") (pinfunction "EN/UV_3") (pintype "input"))
      (node (ref "U7") (pin "2") (pinfunction "OUT2_2") (pintype "output"))
    )
    (net (code "26") (name "Net-(R20-66)") (class "Default")
      (node (ref "R1") (pin "2") (pinfunction "2_2") (pintype "passive"))
      (node (ref "R20") (pin "6") (pinfunction "66_6") (pintype "passive"))
      (node (ref "TP16") (pin "1") (pinfunction "1_1") (pintype "passive"))
      (node (ref "U5") (pin "3") (pinfunction "EN/UV_3") (pintype "input"))
      (node (ref "U6") (pin "3") (pinfunction "EN/UV_3") (pintype "input"))
      (node (ref "U7") (pin "1") (pinfunction "OUT1_1") (pintype "output"))
    )
    (net (code "27") (name "Net-(R20-77)") (class "Default")
      (node (ref "R20") (pin "7") (pinfunction "77_7") (pintype "passive"))
      (node (ref "TP1") (pin "1") (pinfunction "1_1") (pintype "passive"))
      (node (ref "U3") (pin "3") (pinfunction "EN/UV_3") (pintype "input"))
      (node (ref "U7") (pin "14") (pinfunction "OUT3_14") (pintype "output"))
    )
    (net (code "28") (name "Net-(TP2-1)") (class "Default")
      (node (ref "TP2") (pin "TP") (pinfunction "1_TP") (pintype "passive"))
      (node (ref "U3") (pin "4") (pinfunction "PG_4") (pintype "open_collector"))
    )
    (net (code "29") (name "Net-(TP5-1)") (class "Default")
      (node (ref "TP5") (pin "TP") (pinfunction "1_TP") (pintype "passive"))
      (node (ref "U2") (pin "4") (pinfunction "PG_4") (pintype "open_collector"))
    )
    (net (code "30") (name "Net-(TP8-1)") (class "Default")
      (node (ref "TP8") (pin "TP") (pinfunction "1_TP") (pintype "passive"))
      (node (ref "U4") (pin "4") (pinfunction "PG_4") (pintype "open_collector"))
    )
    (net (code "31") (name "Net-(TP11-1)") (class "Default")
      (node (ref "TP11") (pin "TP") (pinfunction "1_TP") (pintype "passive"))
      (node (ref "U5") (pin "4") (pinfunction "PG_4") (pintype "open_collector"))
    )
    (net (code "32") (name "Net-(TP14-1)") (class "Default")
      (node (ref "TP14") (pin "TP") (pinfunction "1_TP") (pintype "passive"))
      (node (ref "U6") (pin "4") (pinfunction "PG_4") (pintype "open_collector"))
    )
    (net (code "33") (name "Net-(TP40-1)") (class "Default")
      (node (ref "TP40") (pin "TP") (pinfunction "1_TP") (pintype "passive"))
      (node (ref "U1") (pin "21") (pinfunction "JAMSYNC_21") (pintype "input"))
    )
    (net (code "34") (name "Net-(TP43-1)") (class "Default")
      (node (ref "R43") (pin "1") (pinfunction "1_1") (pintype "passive"))
      (node (ref "TP43") (pin "TP") (pinfunction "1_TP") (pintype "passive"))
      (node (ref "U13") (pin "4") (pinfunction "OUT_4") (pintype "output"))
    )
    (net (code "35") (name "Net-(TP44-1)") (class "Default")
      (node (ref "R35") (pin "1") (pinfunction "1_1") (pintype "passive"))
      (node (ref "TP44") (pin "TP") (pinfunction "1_TP") (pintype "passive"))
      (node (ref "U12") (pin "4") (pinfunction "OUT_4") (pintype "output"))
    )
    (net (code "36") (name "Net-(TP47-1)") (class "Default")
      (node (ref "R42") (pin "2") (pinfunction "2_2") (pintype "passive"))
      (node (ref "R47") (pin "1") (pinfunction "1_1") (pintype "passive"))
      (node (ref "TP47") (pin "TP") (pinfunction "1_TP") (pintype "passive"))
      (node (ref "U14") (pin "11") (pinfunction "CIN1-_11") (pintype "input"))
    )
    (net (code "37") (name "Net-(TP53-1)") (class "Default")
      (node (ref "TP53") (pin "TP") (pinfunction "1_TP") (pintype "passive"))
      (node (ref "U16") (pin "11") (pinfunction "IO6_11") (pintype "bidirectional"))
    )
    (net (code "38") (name "Net-(TP56-1)") (class "Default")
      (node (ref "TP56") (pin "TP") (pinfunction "1_TP") (pintype "passive"))
      (node (ref "U16") (pin "12") (pinfunction "IO7_12") (pintype "bidirectional"))
    )
    (net (code "39") (name "Net-(TP57-1)") (class "Default")
      (node (ref "R50") (pin "1") (pinfunction "1_1") (pintype "passive"))
      (node (ref "R51") (pin "2") (pinfunction "2_2") (pintype "passive"))
      (node (ref "TP57") (pin "TP") (pinfunction "1_TP") (pintype "passive"))
      (node (ref "U14") (pin "10") (pinfunction "CIN1+_10") (pintype "input"))
    )
    (net (code "40") (name "Net-(U1A-OUT2N)") (class "Default")
      (node (ref "R12") (pin "1") (pinfunction "1_1") (pintype "passive"))
      (node (ref "U1") (pin "12") (pinfunction "OUT2N_12") (pintype "output"))
    )
    (net (code "41") (name "Net-(U1A-OUT2P)") (class "Default")
      (node (ref "R12") (pin "2") (pinfunction "2_2") (pintype "passive"))
      (node (ref "U1") (pin "11") (pinfunction "OUT2P_11") (pintype "output"))
    )
    (net (code "42") (name "Net-(U1A-OUT3N)") (class "Default")
      (node (ref "R13") (pin "1") (pinfunction "1_1") (pintype "passive"))
      (node (ref "U1") (pin "10") (pinfunction "OUT3N_10") (pintype "output"))
    )
    (net (code "43") (name "Net-(U1A-OUT3P)") (class "Default")
      (node (ref "R13") (pin "2") (pinfunction "2_2") (pintype "passive"))
      (node (ref "U1") (pin "9") (pinfunction "OUT3P_9") (pintype "output"))
    )
    (net (code "44") (name "Net-(U1A-OUT4N)") (class "Default")
      (node (ref "R14") (pin "1") (pinfunction "1_1") (pintype "passive"))
      (node (ref "U1") (pin "8") (pinfunction "OUT4N_8") (pintype "output"))
    )
    (net (code "45") (name "Net-(U1A-OUT4P)") (class "Default")
      (node (ref "R14") (pin "2") (pinfunction "2_2") (pintype "passive"))
      (node (ref "U1") (pin "7") (pinfunction "OUT4P_7") (pintype "output"))
    )
    (net (code "46") (name "Net-(U1A-REFCLK)") (class "Default")
      (node (ref "R27") (pin "2") (pinfunction "2_2") (pintype "passive"))
      (node (ref "U1") (pin "20") (pinfunction "REFCLK_20") (pintype "input"))
    )
    (net (code "47") (name "Net-(U1A-TEC+)") (class "Default")
      (node (ref "Q7") (pin "1") (pinfunction "D_1") (pintype "passive"))
      (node (ref "Q7") (pin "2") (pinfunction "D_2") (pintype "passive"))
      (node (ref "Q7") (pin "5") (pinfunction "D_5") (pintype "passive"))
      (node (ref "Q7") (pin "6") (pinfunction "D_6") (pintype "passive"))
      (node (ref "R11") (pin "2") (pinfunction "2_2") (pintype "passive"))
      (node (ref "U1") (pin "23") (pinfunction "TEC+_23") (pintype "passive"))
    )
    (net (code "48") (name "Net-(U2-SET)") (class "Default")
      (node (ref "C13") (pin "1") (pinfunction "1_1") (pintype "passive"))
      (node (ref "R4") (pin "2") (pinfunction "2_2") (pintype "passive"))
      (node (ref "U2") (pin "7") (pinfunction "SET_7") (pintype "input"))
    )
    (net (code "49") (name "Net-(U3-SET)") (class "Default")
      (node (ref "C12") (pin "1") (pinfunction "1_1") (pintype "passive"))
      (node (ref "R3") (pin "2") (pinfunction "2_2") (pintype "passive"))
      (node (ref "U3") (pin "7") (pinfunction "SET_7") (pintype "input"))
    )
    (net (code "50") (name "Net-(U4-SET)") (class "Default")
      (node (ref "C14") (pin "1") (pinfunction "1_1") (pintype "passive"))
      (node (ref "R5") (pin "2") (pinfunction "2_2") (pintype "passive"))
      (node (ref "U4") (pin "7") (pinfunction "SET_7") (pintype "input"))
    )
    (net (code "51") (name "Net-(U5-SET)") (class "Default")
      (node (ref "C15") (pin "1") (pinfunction "1_1") (pintype "passive"))
      (node (ref "R6") (pin "2") (pinfunction "2_2") (pintype "passive"))
      (node (ref "U5") (pin "7") (pinfunction "SET_7") (pintype "input"))
    )
    (net (code "52") (name "Net-(U6-SET)") (class "Default")
      (node (ref "C16") (pin "1") (pinfunction "1_1") (pintype "passive"))
      (node (ref "R7") (pin "2") (pinfunction "2_2") (pintype "passive"))
      (node (ref "U6") (pin "7") (pinfunction "SET_7") (pintype "input"))
    )
    (net (code "53") (name "Net-(U7-1IN+)") (class "Default")
      (node (ref "C17") (pin "1") (pinfunction "1_1") (pintype "passive"))
      (node (ref "R18") (pin "2") (pinfunction "2_2") (pintype "passive"))
      (node (ref "R19") (pin "2") (pinfunction "2_2") (pintype "passive"))
      (node (ref "U7") (pin "11") (pinfunction "4IN+_11") (pintype "input"))
      (node (ref "U7") (pin "5") (pinfunction "2IN+_5") (pintype "input"))
      (node (ref "U7") (pin "7") (pinfunction "1IN+_7") (pintype "input"))
      (node (ref "U7") (pin "9") (pinfunction "3IN+_9") (pintype "input"))
    )
    (net (code "54") (name "Net-(U7-1IN-)") (class "Default")
      (node (ref "R2") (pin "11") (pinfunction "11_11") (pintype "passive"))
      (node (ref "R2") (pin "12") (pinfunction "12_12") (pintype "passive"))
      (node (ref "U7") (pin "6") (pinfunction "1IN-_6") (pintype "input"))
    )
    (net (code "55") (name "Net-(U7-2IN-)") (class "Default")
      (node (ref "R2") (pin "13") (pinfunction "13_13") (pintype "passive"))
      (node (ref "R2") (pin "5") (pinfunction "5_5") (pintype "passive"))
      (node (ref "U7") (pin "4") (pinfunction "2IN-_4") (pintype "input"))
    )
    (net (code "56") (name "Net-(U7-3IN-)") (class "Default")
      (node (ref "R2") (pin "14") (pinfunction "14_14") (pintype "passive"))
      (node (ref "R2") (pin "4") (pinfunction "4_4") (pintype "passive"))
      (node (ref "U7") (pin "8") (pinfunction "3IN-_8") (pintype "input"))
    )
    (net (code "57") (name "Net-(U7-4IN-)") (class "Default")
      (node (ref "R2") (pin "15") (pinfunction "15_15") (pintype "passive"))
      (node (ref "R2") (pin "3") (pinfunction "3_3") (pintype "passive"))
      (node (ref "U7") (pin "10") (pinfunction "4IN-_10") (pintype "input"))
    )
    (net (code "58") (name "Net-(U8-BYPASS)") (class "Default")
      (node (ref "C20") (pin "1") (pinfunction "1_1") (pintype "passive"))
      (node (ref "U8") (pin "4") (pinfunction "BYPASS_4") (pintype "power_in"))
    )
    (net (code "59") (name "Net-(U12-INP)") (class "Default")
      (node (ref "C32") (pin "1") (pinfunction "1_1") (pintype "passive"))
      (node (ref "R36") (pin "1") (pinfunction "1_1") (pintype "passive"))
      (node (ref "R37") (pin "1") (pinfunction "1_1") (pintype "passive"))
      (node (ref "U12") (pin "1") (pinfunction "INP_1") (pintype "input"))
    )
    (net (code "60") (name "Net-(U13-INP)") (class "Default")
      (node (ref "C35") (pin "1") (pinfunction "1_1") (pintype "passive"))
      (node (ref "R44") (pin "1") (pinfunction "1_1") (pintype "passive"))
      (node (ref "R45") (pin "1") (pinfunction "1_1") (pintype "passive"))
      (node (ref "U13") (pin "1") (pinfunction "INP_1") (pintype "input"))
    )
    (net (code "61") (name "Net-(U14-CIN2+)") (class "Default")
      (node (ref "R47") (pin "2") (pinfunction "2_2") (pintype "passive"))
      (node (ref "U14") (pin "12") (pinfunction "REF_12") (pintype "output"))
      (node (ref "U14") (pin "8") (pinfunction "CIN2+_8") (pintype "input"))
    )
    (net (code "62") (name "Net-(U14-INHIBIT)") (class "Default")
      (node (ref "R38") (pin "1") (pinfunction "1_1") (pintype "passive"))
      (node (ref "U14") (pin "5") (pinfunction "INHIBIT_5") (pintype "input"))
    )
    (net (code "63") (name "Net-(U14-IOUT)") (class "Default")
      (node (ref "R50") (pin "2") (pinfunction "2_2") (pintype "passive"))
      (node (ref "U14") (pin "14") (pinfunction "IOUT_14") (pintype "output"))
    )
    (net (code "64") (name "Net-(U14-RS+)") (class "Default")
      (node (ref "C44") (pin "1") (pinfunction "1_1") (pintype "passive"))
      (node (ref "Q6") (pin "1") (pinfunction "D_1") (pintype "passive"))
      (node (ref "Q6") (pin "2") (pinfunction "D_2") (pintype "passive"))
      (node (ref "Q6") (pin "5") (pinfunction "D_5") (pintype "passive"))
      (node (ref "Q6") (pin "6") (pinfunction "D_6") (pintype "passive"))
      (node (ref "R63") (pin "1") (pinfunction "1_1") (pintype "passive"))
      (node (ref "U14") (pin "16") (pinfunction "RS+_16") (pintype "passive"))
    )
    (net (code "65") (name "Net-(U16-~{RESET})") (class "Default")
      (node (ref "R72") (pin "1") (pinfunction "1_1") (pintype "passive"))
      (node (ref "U16") (pin "13") (pinfunction "~{RESET}_13") (pintype "input"))
    )
    (net (code "66") (name "Net-(X1-OUT)") (class "Default")
      (node (ref "R27") (pin "1") (pinfunction "1_1") (pintype "passive"))
      (node (ref "X1") (pin "3") (pinfunction "OUT_3") (pintype "output"))
    )
    (net (code "67") (name "ON{slash}~{OFF}") (class "Default")
      (node (ref "C34") (pin "1") (pinfunction "1_1") (pintype "passive"))
      (node (ref "Q4") (pin "1") (pinfunction "G_1") (pintype "passive"))
      (node (ref "R46") (pin "2") (pinfunction "2_2") (pintype "passive"))
      (node (ref "R49") (pin "2") (pinfunction "2_2") (pintype "passive"))
      (node (ref "TP50") (pin "TP") (pinfunction "1_TP") (pintype "passive"))
      (node (ref "U14") (pin "1") (pinfunction "VCC_1") (pintype "power_in"))
      (node (ref "U16") (pin "8") (pinfunction "IO3_8") (pintype "bidirectional"))
    )
    (net (code "68") (name "OPD_PWR") (class "Default")
      (node (ref "J4") (pin "15") (pinfunction "15_15") (pintype "passive"))
      (node (ref "J4") (pin "16") (pinfunction "16_16") (pintype "passive"))
      (node (ref "R71") (pin "1") (pinfunction "1_1") (pintype "passive"))
    )
    (net (code "69") (name "OPD_SCL") (class "Default")
      (node (ref "J4") (pin "13") (pinfunction "13_13") (pintype "passive"))
      (node (ref "J4") (pin "14") (pinfunction "14_14") (pintype "passive"))
      (node (ref "R48") (pin "1") (pinfunction "1_1") (pintype "passive"))
    )
    (net (code "70") (name "OPD_SDA") (class "Default")
      (node (ref "J4") (pin "11") (pinfunction "11_11") (pintype "passive"))
      (node (ref "J4") (pin "12") (pinfunction "12_12") (pintype "passive"))
      (node (ref "R41") (pin "1") (pinfunction "1_1") (pintype "passive"))
    )
    (net (code "71") (name "OUT1N") (class "Default")
      (node (ref "J2") (pin "5") (pinfunction "5_5") (pintype "passive"))
      (node (ref "J2") (pin "6") (pinfunction "6_6") (pintype "passive"))
      (node (ref "U1") (pin "14") (pinfunction "OUT1N_14") (pintype "output"))
    )
    (net (code "72") (name "OUT1P") (class "Default")
      (node (ref "J2") (pin "7") (pinfunction "7_7") (pintype "passive"))
      (node (ref "J2") (pin "8") (pinfunction "8_8") (pintype "passive"))
      (node (ref "U1") (pin "13") (pinfunction "OUT1P_13") (pintype "output"))
    )
    (net (code "73") (name "PB6{slash}SCL") (class "Default")
      (node (ref "TP67") (pin "TP") (pinfunction "1_TP") (pintype "passive"))
      (node (ref "U16") (pin "4") (pinfunction "IO0_4") (pintype "bidirectional"))
    )
    (net (code "74") (name "PB7{slash}SDA") (class "Default")
      (node (ref "TP68") (pin "TP") (pinfunction "1_TP") (pintype "passive"))
      (node (ref "U16") (pin "5") (pinfunction "IO1_5") (pintype "bidirectional"))
    )
    (net (code "75") (name "PEN-SCL-FILT") (class "Default")
      (node (ref "Q3") (pin "6") (pinfunction "D_6") (pintype "passive"))
      (node (ref "R37") (pin "2") (pinfunction "2_2") (pintype "passive"))
      (node (ref "R65") (pin "1") (pinfunction "1_1") (pintype "passive"))
      (node (ref "R67") (pin "1") (pinfunction "1_1") (pintype "passive"))
      (node (ref "R69") (pin "1") (pinfunction "1_1") (pintype "passive"))
      (node (ref "TP42") (pin "TP") (pinfunction "1_TP") (pintype "passive"))
      (node (ref "U16") (pin "15") (pinfunction "SCL_15") (pintype "input"))
    )
    (net (code "76") (name "PEN-SDA-FILT") (class "Default")
      (node (ref "Q3") (pin "4") (pinfunction "D_4") (pintype "passive"))
      (node (ref "R45") (pin "2") (pinfunction "2_2") (pintype "passive"))
      (node (ref "R66") (pin "2") (pinfunction "2_2") (pintype "passive"))
      (node (ref "R68") (pin "2") (pinfunction "2_2") (pintype "passive"))
      (node (ref "R70") (pin "2") (pinfunction "2_2") (pintype "passive"))
      (node (ref "TP41") (pin "TP") (pinfunction "1_TP") (pintype "passive"))
      (node (ref "U16") (pin "16") (pinfunction "SDA_16") (pintype "bidirectional"))
    )
    (net (code "77") (name "POUT") (class "Default")
      (node (ref "TP64") (pin "TP") (pinfunction "1_TP") (pintype "passive"))
      (node (ref "U14") (pin "13") (pinfunction "POUT_13") (pintype "output"))
    )
    (net (code "78") (name "REFCLK_ENABLE") (class "Default")
      (node (ref "R20") (pin "3") (pinfunction "33_3") (pintype "passive"))
      (node (ref "TP27") (pin "1") (pinfunction "1_1") (pintype "passive"))
      (node (ref "U7") (pin "13") (pinfunction "OUT4_13") (pintype "output"))
      (node (ref "X1") (pin "1") (pinfunction "EN_1") (pintype "passive"))
    )
    (net (code "79") (name "SENSOR_ENABLE") (class "Default")
      (node (ref "J2") (pin "13") (pinfunction "13_13") (pintype "passive"))
      (node (ref "J2") (pin "14") (pinfunction "14_14") (pintype "passive"))
      (node (ref "R8") (pin "1") (pinfunction "1_1") (pintype "passive"))
      (node (ref "TP39") (pin "1") (pinfunction "1_1") (pintype "passive"))
    )
    (net (code "80") (name "SPI_CLK") (class "Default")
      (node (ref "J2") (pin "17") (pinfunction "17_17") (pintype "passive"))
      (node (ref "J2") (pin "18") (pinfunction "18_18") (pintype "passive"))
      (node (ref "U1") (pin "26") (pinfunction "SDCLK_26") (pintype "input"))
    )
    (net (code "81") (name "SPI_MISO") (class "Default")
      (node (ref "J2") (pin "15") (pinfunction "15_15") (pintype "passive"))
      (node (ref "J2") (pin "16") (pinfunction "16_16") (pintype "passive"))
      (node (ref "U1") (pin "27") (pinfunction "SDOUT_27") (pintype "output"))
    )
    (net (code "82") (name "SPI_MOSI") (class "Default")
      (node (ref "J2") (pin "19") (pinfunction "19_19") (pintype "passive"))
      (node (ref "J2") (pin "20") (pinfunction "20_20") (pintype "passive"))
      (node (ref "U1") (pin "25") (pinfunction "SDIN_25") (pintype "input"))
    )
    (net (code "83") (name "TEC_ENABLE") (class "Default")
      (node (ref "J2") (pin "10") (pinfunction "10_10") (pintype "passive"))
      (node (ref "J2") (pin "9") (pinfunction "9_9") (pintype "passive"))
      (node (ref "Q8") (pin "1") (pinfunction "G_1") (pintype "passive"))
      (node (ref "R10") (pin "2") (pinfunction "2_2") (pintype "passive"))
    )
    (net (code "84") (name "THERM+") (class "Default")
      (node (ref "J2") (pin "11") (pinfunction "11_11") (pintype "passive"))
      (node (ref "J2") (pin "12") (pinfunction "12_12") (pintype "passive"))
      (node (ref "U1") (pin "1") (pinfunction "THERM+_1") (pintype "passive"))
    )
    (net (code "85") (name "TXCLKN") (class "Default")
      (node (ref "J2") (pin "1") (pinfunction "1_1") (pintype "passive"))
      (node (ref "J2") (pin "2") (pinfunction "2_2") (pintype "passive"))
      (node (ref "U1") (pin "16") (pinfunction "TXCLKN_16") (pintype "output"))
    )
    (net (code "86") (name "TXCLKP") (class "Default")
      (node (ref "J2") (pin "3") (pinfunction "3_3") (pintype "passive"))
      (node (ref "J2") (pin "4") (pinfunction "4_4") (pintype "passive"))
      (node (ref "U1") (pin "15") (pinfunction "TXCLKP_15") (pintype "output"))
    )
    (net (code "87") (name "VBUS") (class "Default")
      (node (ref "J4") (pin "21") (pinfunction "21_21") (pintype "passive"))
      (node (ref "J4") (pin "22") (pinfunction "22_22") (pintype "passive"))
      (node (ref "J4") (pin "23") (pinfunction "23_23") (pintype "passive"))
      (node (ref "J4") (pin "24") (pinfunction "24_24") (pintype "passive"))
      (node (ref "J4") (pin "25") (pinfunction "25_25") (pintype "passive"))
      (node (ref "J4") (pin "26") (pinfunction "26_26") (pintype "passive"))
      (node (ref "Q6") (pin "4") (pinfunction "S_4") (pintype "passive"))
      (node (ref "R52") (pin "2") (pinfunction "2_2") (pintype "passive"))
    )
    (net (code "88") (name "VBUSP") (class "Default")
      (node (ref "C1") (pin "1") (pinfunction "1_1") (pintype "passive"))
      (node (ref "C18") (pin "1") (pinfunction "1_1") (pintype "passive"))
      (node (ref "C2") (pin "1") (pinfunction "1_1") (pintype "passive"))
      (node (ref "C21") (pin "1") (pinfunction "1_1") (pintype "passive"))
      (node (ref "C3") (pin "1") (pinfunction "1_1") (pintype "passive"))
      (node (ref "C33") (pin "2") (pinfunction "2_2") (pintype "passive"))
      (node (ref "C4") (pin "1") (pinfunction "1_1") (pintype "passive"))
      (node (ref "C5") (pin "1") (pinfunction "1_1") (pintype "passive"))
      (node (ref "Q5") (pin "1") (pinfunction "D_1") (pintype "passive"))
      (node (ref "Q5") (pin "2") (pinfunction "D_2") (pintype "passive"))
      (node (ref "Q5") (pin "5") (pinfunction "D_5") (pintype "passive"))
      (node (ref "Q5") (pin "6") (pinfunction "D_6") (pintype "passive"))
      (node (ref "Q7") (pin "4") (pinfunction "S_4") (pintype "passive"))
      (node (ref "R61") (pin "2") (pinfunction "2_2") (pintype "passive"))
      (node (ref "R9") (pin "2") (pinfunction "2_2") (pintype "passive"))
      (node (ref "TP55") (pin "TP") (pinfunction "1_TP") (pintype "passive"))
      (node (ref "U2") (pin "1") (pinfunction "IN_1") (pintype "power_in"))
      (node (ref "U2") (pin "2") (pinfunction "IN_2") (pintype "power_in"))
      (node (ref "U2") (pin "6") (pinfunction "PGFB_6") (pintype "passive"))
      (node (ref "U3") (pin "1") (pinfunction "IN_1") (pintype "power_in"))
      (node (ref "U3") (pin "2") (pinfunction "IN_2") (pintype "power_in"))
      (node (ref "U3") (pin "6") (pinfunction "PGFB_6") (pintype "passive"))
      (node (ref "U4") (pin "1") (pinfunction "IN_1") (pintype "power_in"))
      (node (ref "U4") (pin "2") (pinfunction "IN_2") (pintype "power_in"))
      (node (ref "U4") (pin "6") (pinfunction "PGFB_6") (pintype "passive"))
      (node (ref "U5") (pin "1") (pinfunction "IN_1") (pintype "power_in"))
      (node (ref "U5") (pin "2") (pinfunction "IN_2") (pintype "power_in"))
      (node (ref "U5") (pin "6") (pinfunction "PGFB_6") (pintype "passive"))
      (node (ref "U6") (pin "1") (pinfunction "IN_1") (pintype "power_in"))
      (node (ref "U6") (pin "2") (pinfunction "IN_2") (pintype "power_in"))
      (node (ref "U6") (pin "6") (pinfunction "PGFB_6") (pintype "passive"))
      (node (ref "U8") (pin "1") (pinfunction "VIN_1") (pintype "power_in"))
      (node (ref "U8") (pin "3") (pinfunction "EN_3") (pintype "input"))
    )
    (net (code "89") (name "VDETCOM-2.9V") (class "Default")
      (node (ref "C102") (pin "1") (pinfunction "1_1") (pintype "passive"))
      (node (ref "C6") (pin "1") (pinfunction "1_1") (pintype "passive"))
      (node (ref "TP22") (pin "TP") (pinfunction "1_TP") (pintype "passive"))
      (node (ref "U1") (pin "31") (pinfunction "VDETCOM~{2.9V}_31") (pintype "power_in"))
      (node (ref "U3") (pin "10") (pinfunction "OUT_10") (pintype "power_in"))
      (node (ref "U3") (pin "9") (pinfunction "OUTS_9") (pintype "power_in"))
    )
    (net (code "90") (name "VPD") (class "Default")
      (node (ref "C39") (pin "2") (pinfunction "2_2") (pintype "passive"))
      (node (ref "R32") (pin "2") (pinfunction "2_2") (pintype "passive"))
      (node (ref "R36") (pin "2") (pinfunction "2_2") (pintype "passive"))
      (node (ref "R44") (pin "2") (pinfunction "2_2") (pintype "passive"))
      (node (ref "R53") (pin "2") (pinfunction "2_2") (pintype "passive"))
      (node (ref "R55") (pin "2") (pinfunction "2_2") (pintype "passive"))
      (node (ref "R57") (pin "2") (pinfunction "2_2") (pintype "passive"))
      (node (ref "R71") (pin "2") (pinfunction "2_2") (pintype "passive"))
      (node (ref "R72") (pin "2") (pinfunction "2_2") (pintype "passive"))
      (node (ref "TP63") (pin "TP") (pinfunction "1_TP") (pintype "passive"))
      (node (ref "U12") (pin "5") (pinfunction "VDD_5") (pintype "power_in"))
      (node (ref "U13") (pin "5") (pinfunction "VDD_5") (pintype "power_in"))
      (node (ref "U16") (pin "14") (pinfunction "V+_14") (pintype "power_in"))
    )
    (net (code "91") (name "VPH-3.3V") (class "Default")
      (node (ref "C100") (pin "1") (pinfunction "1_1") (pintype "passive"))
      (node (ref "C9") (pin "1") (pinfunction "1_1") (pintype "passive"))
      (node (ref "TP25") (pin "TP") (pinfunction "1_TP") (pintype "passive"))
      (node (ref "U1") (pin "19") (pinfunction "VPH-3.3V_19") (pintype "power_in"))
      (node (ref "U5") (pin "10") (pinfunction "OUT_10") (pintype "power_in"))
      (node (ref "U5") (pin "9") (pinfunction "OUTS_9") (pintype "power_in"))
    )
    (net (code "92") (name "VPL-1.6V") (class "Default")
      (node (ref "C101") (pin "1") (pinfunction "1_1") (pintype "passive"))
      (node (ref "C8") (pin "1") (pinfunction "1_1") (pintype "passive"))
      (node (ref "TP24") (pin "TP") (pinfunction "1_TP") (pintype "passive"))
      (node (ref "U1") (pin "18") (pinfunction "VPL-1.6V_18") (pintype "power_in"))
      (node (ref "U4") (pin "10") (pinfunction "OUT_10") (pintype "power_in"))
      (node (ref "U4") (pin "9") (pinfunction "OUTS_9") (pintype "power_in"))
    )
    (net (code "93") (name "VPOS-3.3V") (class "Default")
      (node (ref "C10") (pin "1") (pinfunction "1_1") (pintype "passive"))
      (node (ref "C103") (pin "1") (pinfunction "1_1") (pintype "passive"))
      (node (ref "TP26") (pin "TP") (pinfunction "1_TP") (pintype "passive"))
      (node (ref "U1") (pin "30") (pinfunction "VPOS-3.3V_30") (pintype "power_in"))
      (node (ref "U6") (pin "10") (pinfunction "OUT_10") (pintype "power_in"))
      (node (ref "U6") (pin "9") (pinfunction "OUTS_9") (pintype "power_in"))
    )
    (net (code "94") (name "VPOUT-0.9V") (class "Default")
      (node (ref "C104") (pin "1") (pinfunction "1_1") (pintype "passive"))
      (node (ref "C7") (pin "1") (pinfunction "1_1") (pintype "passive"))
      (node (ref "TP23") (pin "TP") (pinfunction "1_TP") (pintype "passive"))
      (node (ref "U1") (pin "5") (pinfunction "VPOUT-0.9V_5") (pintype "power_in"))
      (node (ref "U2") (pin "10") (pinfunction "OUT_10") (pintype "power_in"))
      (node (ref "U2") (pin "9") (pinfunction "OUTS_9") (pintype "power_in"))
    )
    (net (code "95") (name "unconnected-(J4-Pad1)") (class "Default")
      (node (ref "J4") (pin "1") (pinfunction "1_1") (pintype "passive"))
    )
    (net (code "96") (name "unconnected-(J4-Pad2)") (class "Default")
      (node (ref "J4") (pin "2") (pinfunction "2_2") (pintype "passive"))
    )
    (net (code "97") (name "unconnected-(J4-Pad3)") (class "Default")
      (node (ref "J4") (pin "3") (pinfunction "3_3") (pintype "passive"))
    )
    (net (code "98") (name "unconnected-(J4-Pad4)") (class "Default")
      (node (ref "J4") (pin "4") (pinfunction "4_4") (pintype "passive"))
    )
    (net (code "99") (name "unconnected-(J4-Pad5)") (class "Default")
      (node (ref "J4") (pin "5") (pinfunction "5_5") (pintype "passive"))
    )
    (net (code "100") (name "unconnected-(J4-Pad6)") (class "Default")
      (node (ref "J4") (pin "6") (pinfunction "6_6") (pintype "passive"))
    )
    (net (code "101") (name "unconnected-(J4-Pad7)") (class "Default")
      (node (ref "J4") (pin "7") (pinfunction "7_7") (pintype "passive"))
    )
    (net (code "102") (name "unconnected-(J4-Pad8)") (class "Default")
      (node (ref "J4") (pin "8") (pinfunction "8_8") (pintype "passive"))
    )
    (net (code "103") (name "unconnected-(J4-Pad9)") (class "Default")
      (node (ref "J4") (pin "9") (pinfunction "9_9") (pintype "passive"))
    )
    (net (code "104") (name "unconnected-(J4-Pad10)") (class "Default")
      (node (ref "J4") (pin "10") (pinfunction "10_10") (pintype "passive"))
    )
    (net (code "105") (name "unconnected-(J4-Pad17)") (class "Default")
      (node (ref "J4") (pin "17") (pinfunction "17_17") (pintype "passive"))
    )
    (net (code "106") (name "unconnected-(J4-Pad18)") (class "Default")
      (node (ref "J4") (pin "18") (pinfunction "18_18") (pintype "passive"))
    )
    (net (code "107") (name "unconnected-(J4-Pad19)") (class "Default")
      (node (ref "J4") (pin "19") (pinfunction "19_19") (pintype "passive"))
    )
    (net (code "108") (name "unconnected-(J4-Pad20)") (class "Default")
      (node (ref "J4") (pin "20") (pinfunction "20_20") (pintype "passive"))
    )
    (net (code "109") (name "unconnected-(J4-Pad33)") (class "Default")
      (node (ref "J4") (pin "33") (pinfunction "33_33") (pintype "passive"))
    )
    (net (code "110") (name "unconnected-(J4-Pad34)") (class "Default")
      (node (ref "J4") (pin "34") (pinfunction "34_34") (pintype "passive"))
    )
    (net (code "111") (name "unconnected-(J4-Pad35)") (class "Default")
      (node (ref "J4") (pin "35") (pinfunction "35_35") (pintype "passive"))
    )
    (net (code "112") (name "unconnected-(J4-Pad36)") (class "Default")
      (node (ref "J4") (pin "36") (pinfunction "36_36") (pintype "passive"))
    )
    (net (code "113") (name "unconnected-(R2-Pad8)") (class "Default")
      (node (ref "R2") (pin "8") (pinfunction "8_8") (pintype "passive"))
    )
    (net (code "114") (name "unconnected-(R2-Pad9)") (class "Default")
      (node (ref "R2") (pin "9") (pinfunction "9_9") (pintype "passive"))
    )
    (net (code "115") (name "unconnected-(R20-11-Pad1)") (class "Default")
      (node (ref "R20") (pin "1") (pinfunction "11_1") (pintype "passive"))
    )
    (net (code "116") (name "unconnected-(R20-22-Pad2)") (class "Default")
      (node (ref "R20") (pin "2") (pinfunction "22_2") (pintype "passive"))
    )
    (net (code "117") (name "unconnected-(R20-88-Pad8)") (class "Default")
      (node (ref "R20") (pin "8") (pinfunction "88_8") (pintype "passive"))
    )
    (net (code "118") (name "unconnected-(R20-99-Pad9)") (class "Default")
      (node (ref "R20") (pin "9") (pinfunction "99_9") (pintype "passive"))
    )
    (net (code "119") (name "unconnected-(U1A-ABITOUT-Pad24)") (class "Default")
      (node (ref "U1") (pin "24") (pinfunction "ABITOUT_24") (pintype "output"))
    )
    (net (code "120") (name "~{FAULT}") (class "Default")
      (node (ref "Q2") (pin "3") (pinfunction "D_3") (pintype "passive"))
      (node (ref "R32") (pin "1") (pinfunction "1_1") (pintype "passive"))
      (node (ref "TP45") (pin "TP") (pinfunction "1_TP") (pintype "passive"))
      (node (ref "U16") (pin "7") (pinfunction "IO2_7") (pintype "bidirectional"))
    )
    (net (code "121") (name "~{SD}") (class "Default")
      (node (ref "J4") (pin "39") (pinfunction "39_39") (pintype "passive"))
      (node (ref "J4") (pin "40") (pinfunction "40_40") (pintype "passive"))
    )
  )
)
